# electrosteel2020_10_arrange6_synthboards.net
KiCad netlist of a schematic drawn in EAGLE
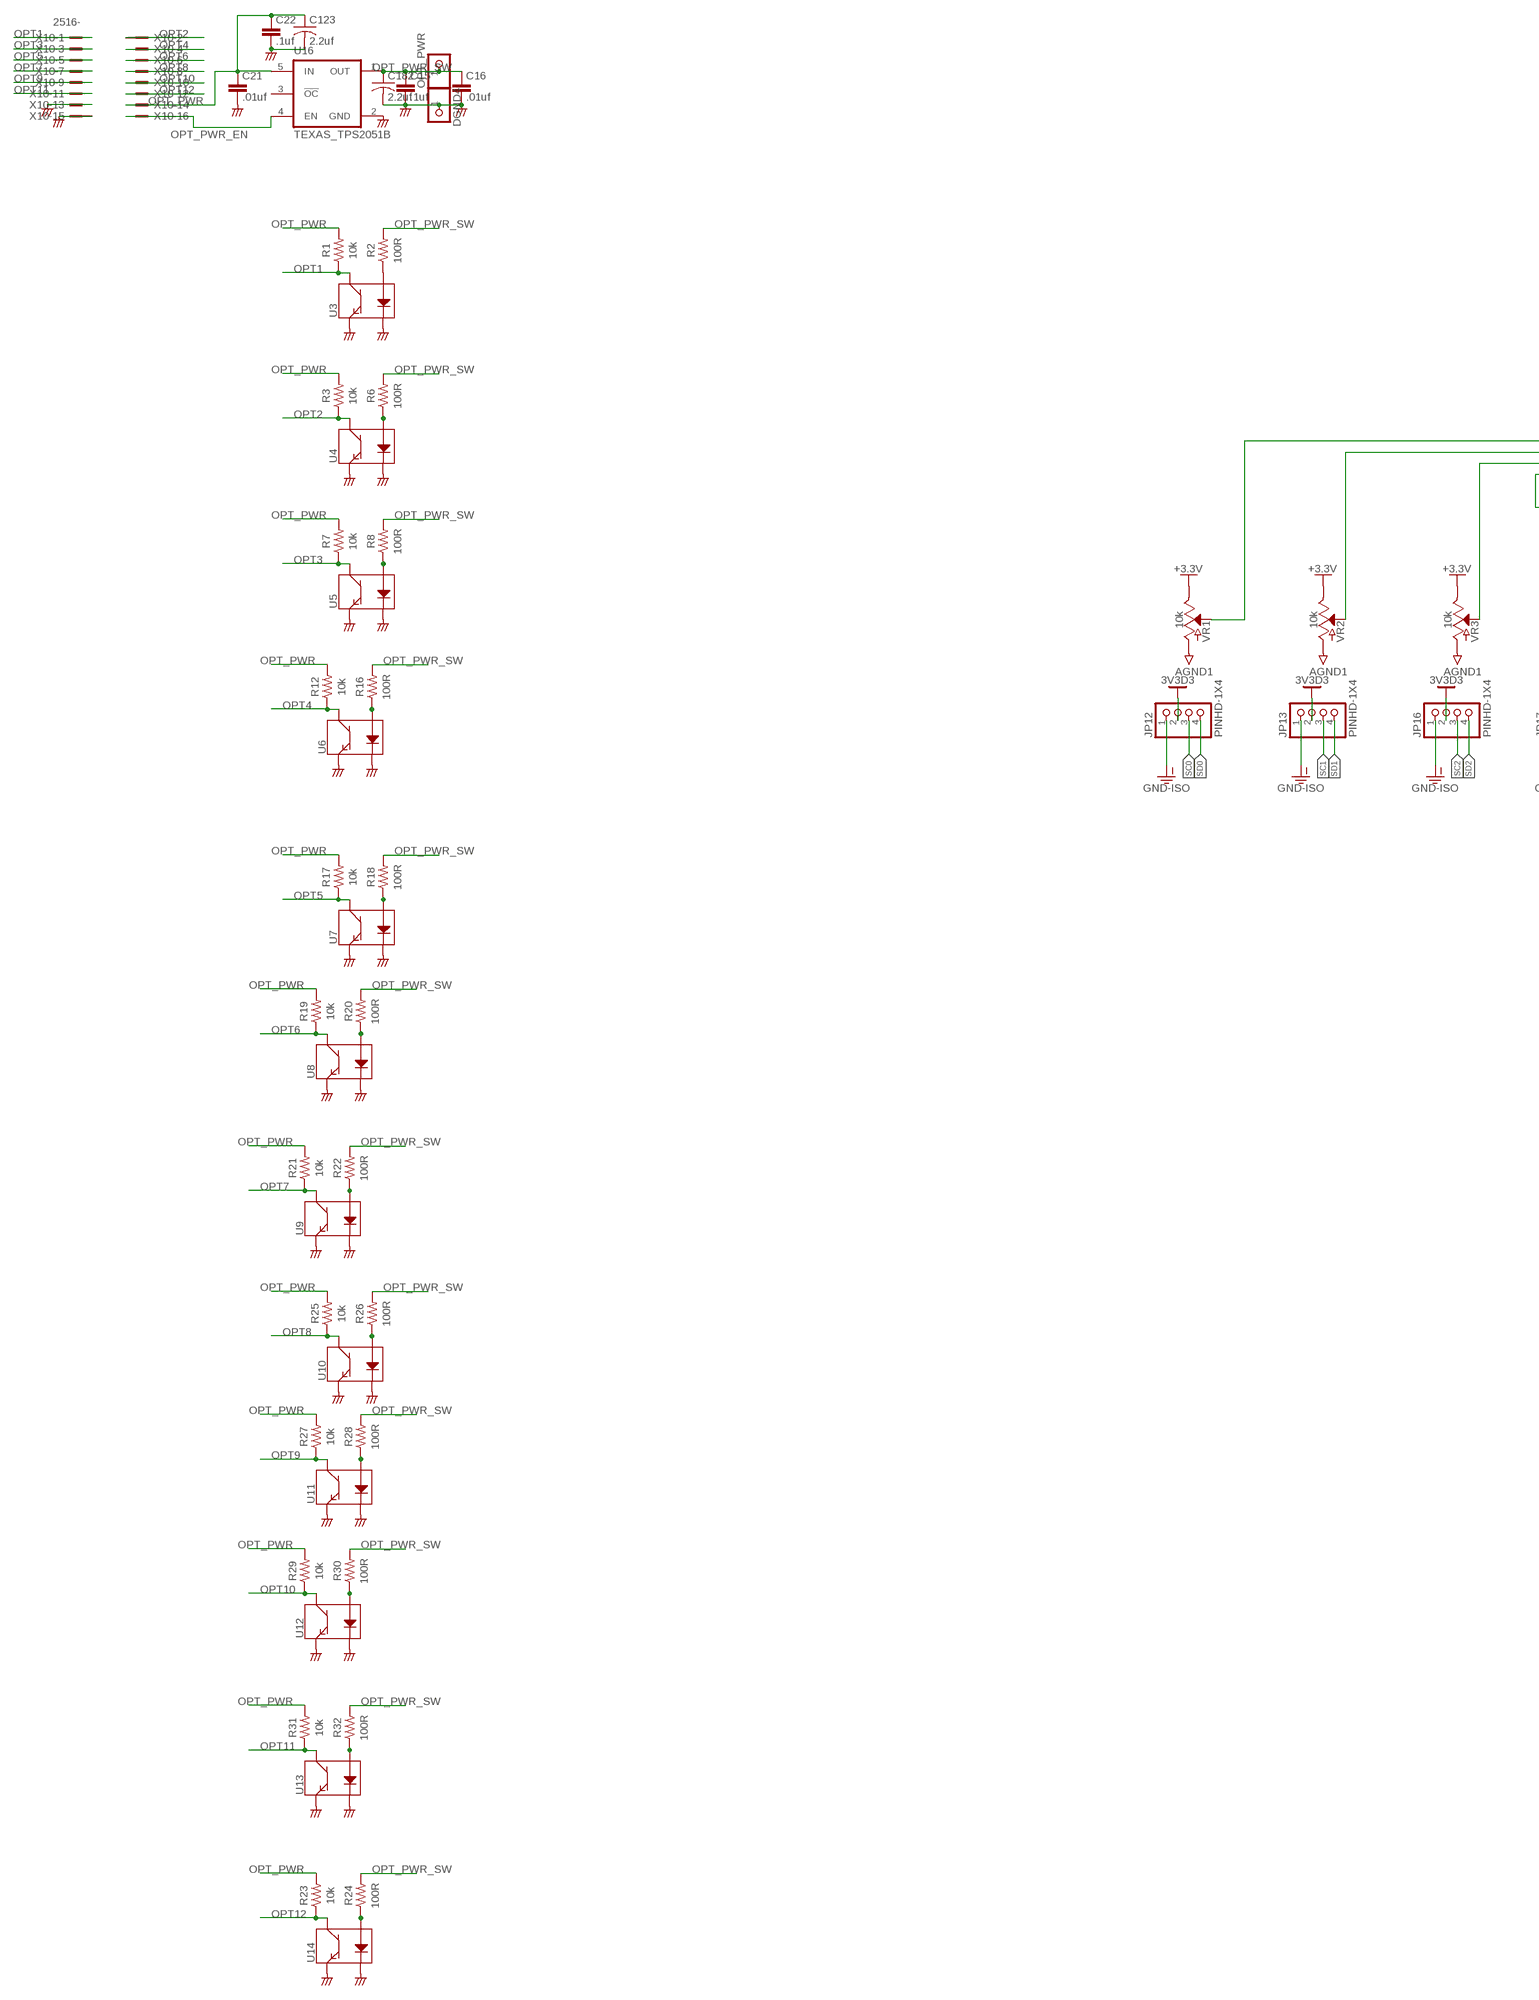
[diagram p0: schematic, sheet 1, part 1 of 3]
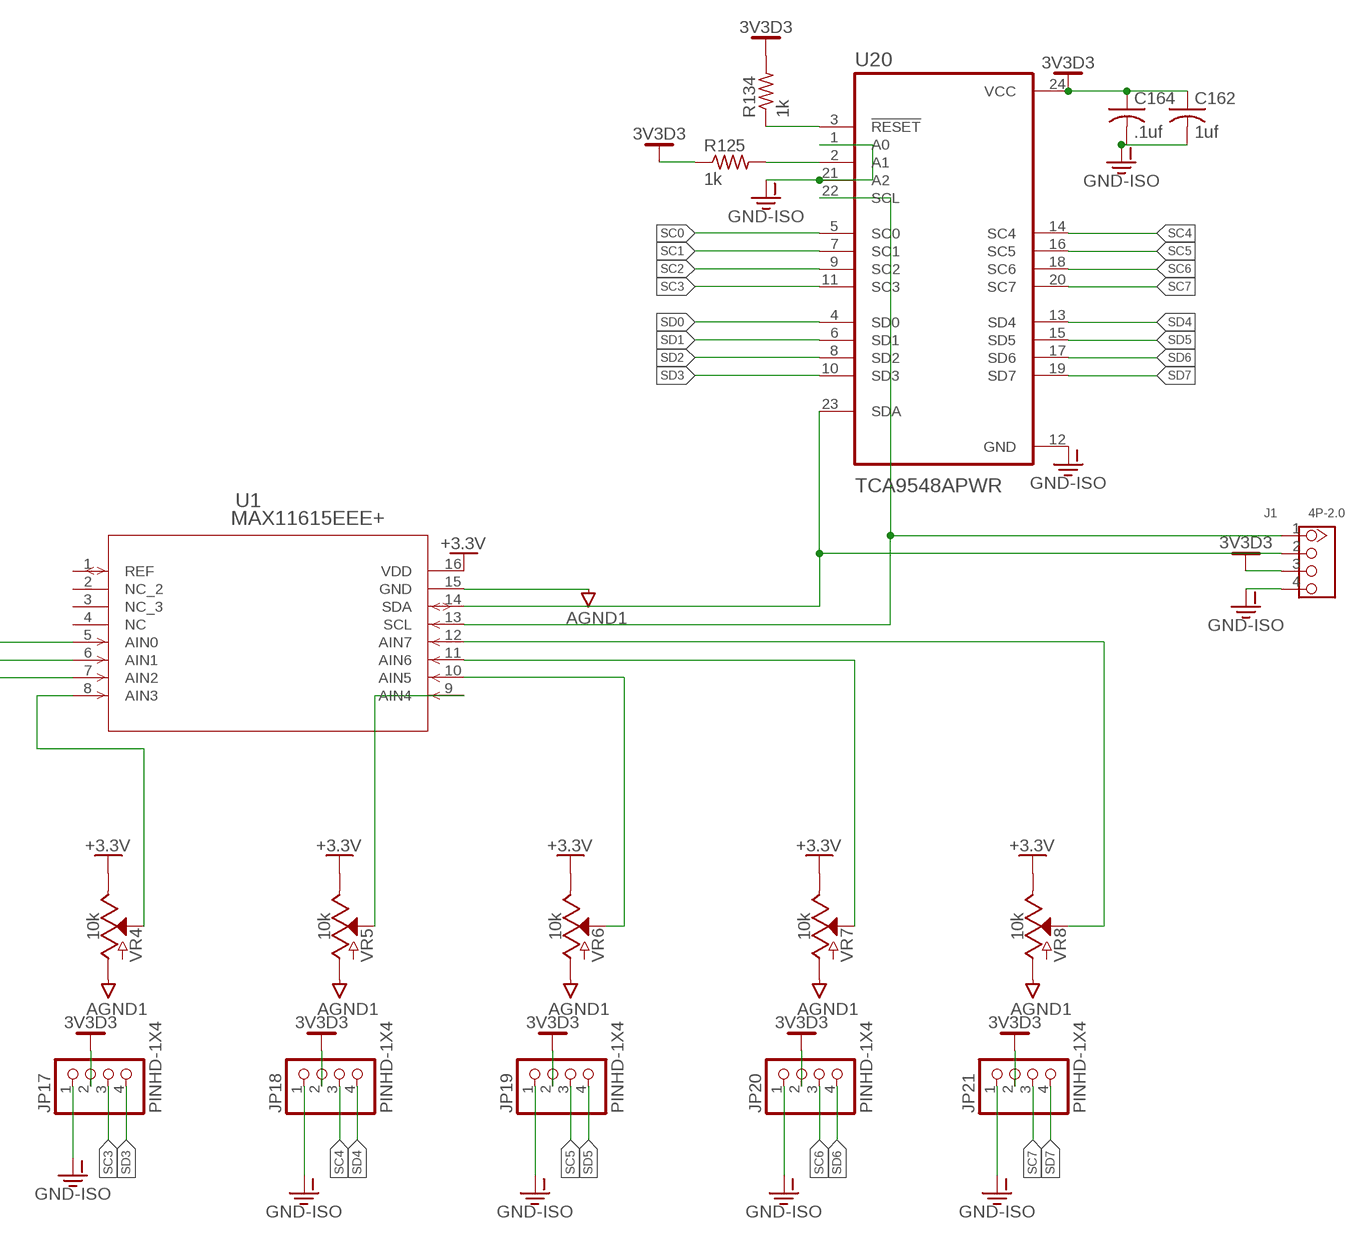
[diagram p1: schematic, sheet 1, part 2 of 3]
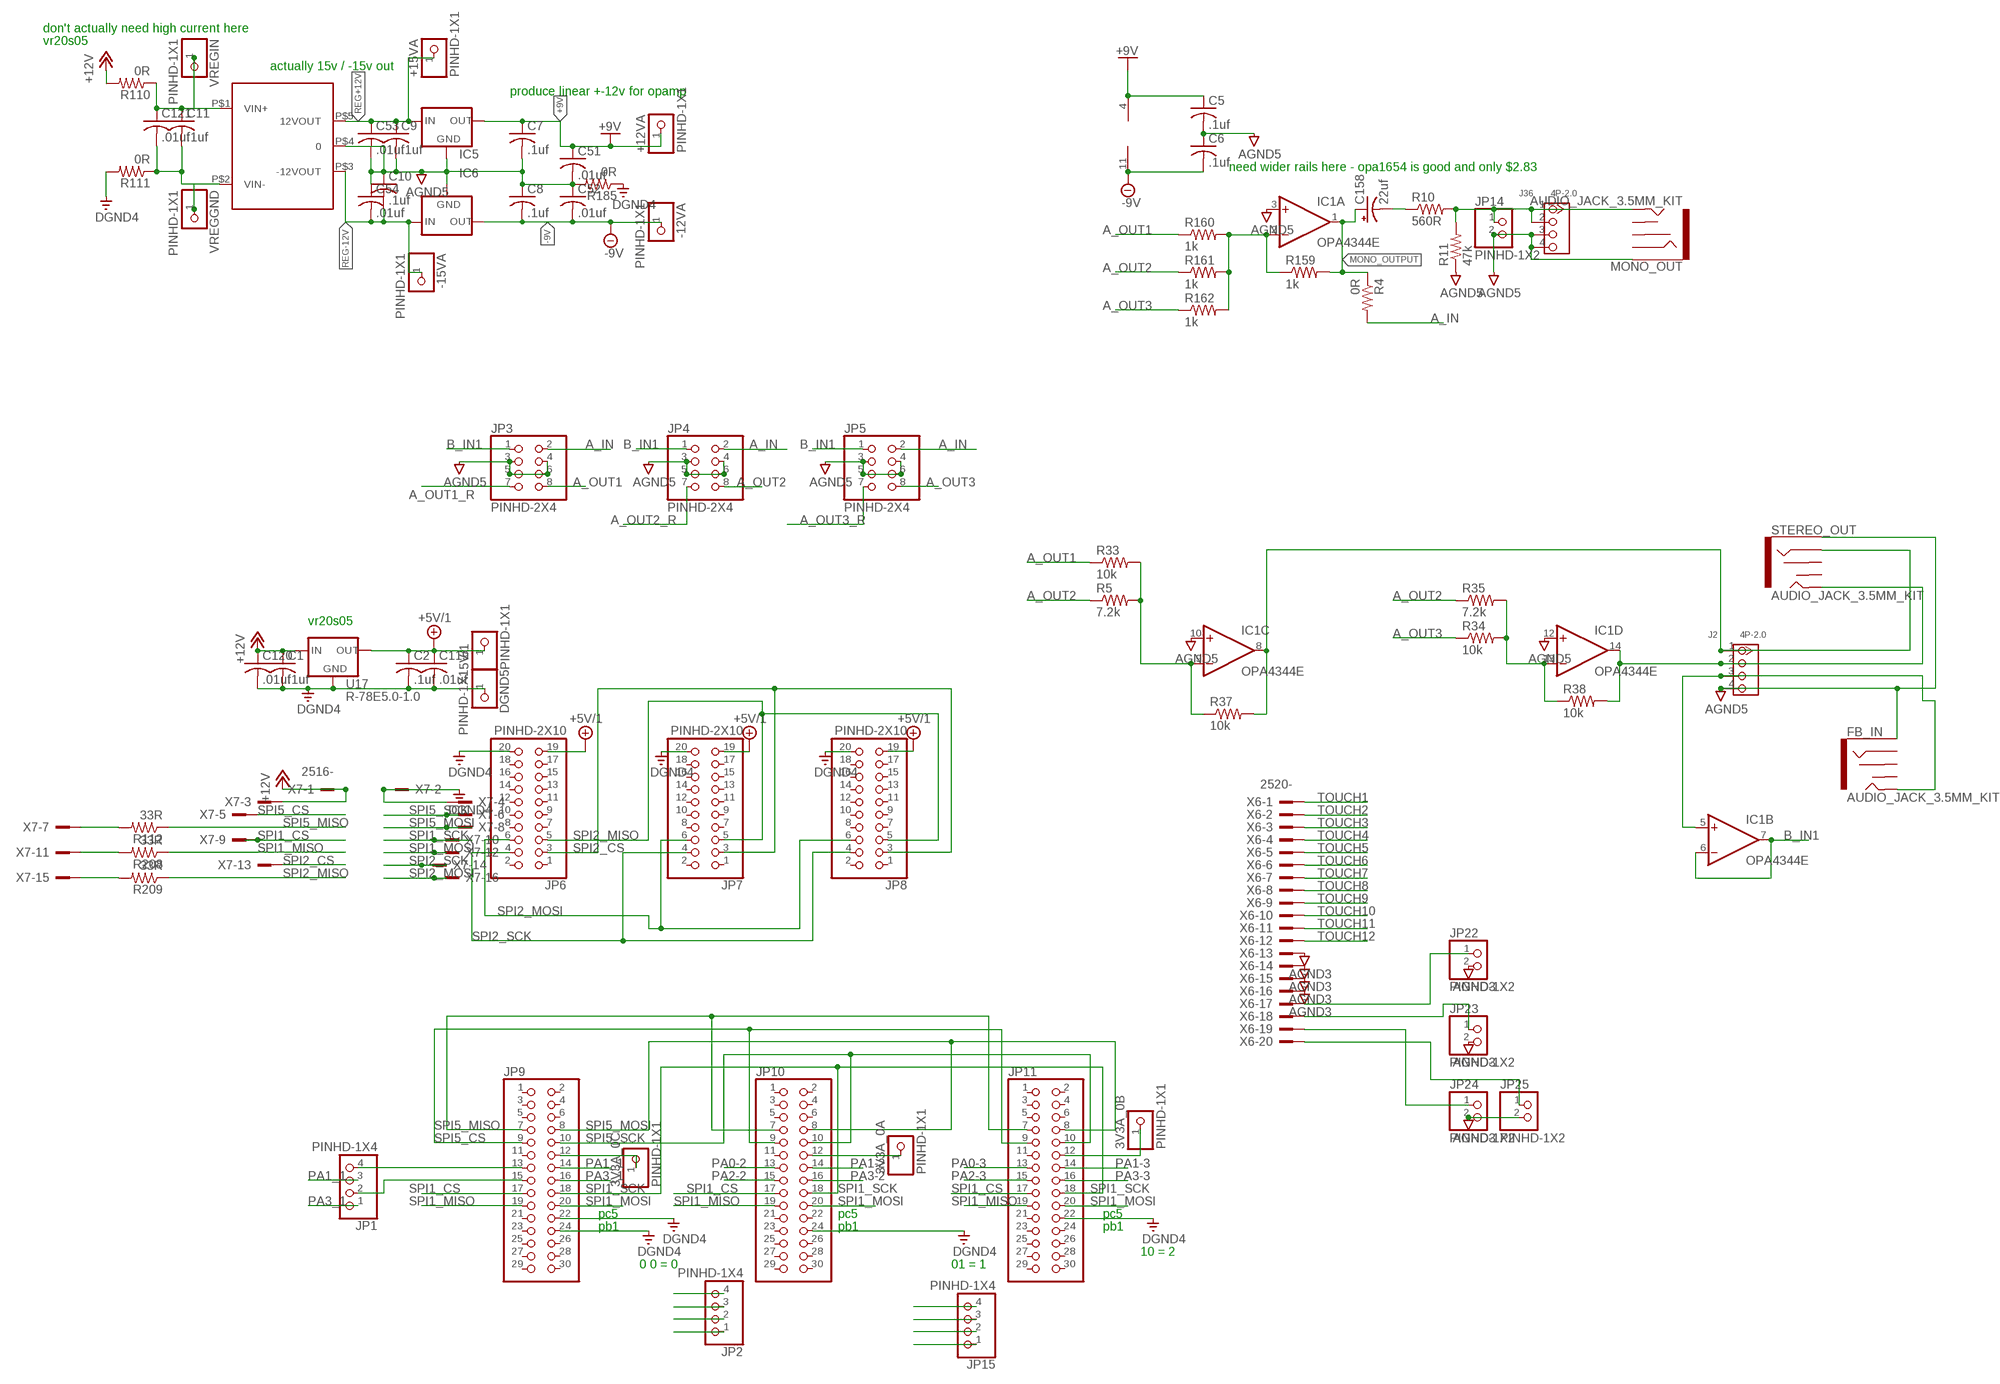
[diagram p2: schematic, sheet 1, part 3 of 3]

(export (version "E")
  (design (tool "Eeschema 10.0.6"))
  (components
    (comp (ref "+12VA")
      (value "PINHD-1X1")
      (footprint "eagle-import:1X01")
      (fields (field (name "PARTNO") "*DNP"))
      (libsource (lib "eagle-import") (part "PINHD-1X1"))
    )
    (comp (ref "+15VA")
      (value "PINHD-1X1")
      (footprint "eagle-import:1X01")
      (fields (field (name "PARTNO") "*DNP"))
      (libsource (lib "eagle-import") (part "PINHD-1X1"))
    )
    (comp (ref "-12VA")
      (value "PINHD-1X1")
      (footprint "eagle-import:1X01")
      (fields (field (name "PARTNO") "*DNP"))
      (libsource (lib "eagle-import") (part "PINHD-1X1"))
    )
    (comp (ref "-15VA")
      (value "PINHD-1X1")
      (footprint "eagle-import:1X01")
      (fields (field (name "PARTNO") "*DNP"))
      (libsource (lib "eagle-import") (part "PINHD-1X1"))
    )
    (comp (ref "3V3A_0A")
      (value "PINHD-1X1")
      (footprint "eagle-import:1X01")
      (fields (field (name "PARTNO") "*DNP"))
      (libsource (lib "eagle-import") (part "PINHD-1X1"))
    )
    (comp (ref "3V3A_0B")
      (value "PINHD-1X1")
      (footprint "eagle-import:1X01")
      (fields (field (name "PARTNO") "*DNP"))
      (libsource (lib "eagle-import") (part "PINHD-1X1"))
    )
    (comp (ref "3V3A_0C")
      (value "PINHD-1X1")
      (footprint "eagle-import:1X01")
      (fields (field (name "PARTNO") "*DNP"))
      (libsource (lib "eagle-import") (part "PINHD-1X1"))
    )
    (comp (ref "5V/1")
      (value "PINHD-1X1")
      (footprint "eagle-import:1X01")
      (fields (field (name "PARTNO") "*DNP"))
      (libsource (lib "eagle-import") (part "PINHD-1X1"))
    )
    (comp (ref "C1")
      (value ".1uf")
      (footprint "eagle-import:C0603")
      (fields (field (name "PARTNO") "TMK063B7103KP-F"))
      (libsource (lib "eagle-import") (part "rcl_334_C-USC0603"))
    )
    (comp (ref "C2")
      (value ".1uf")
      (footprint "eagle-import:C0603")
      (fields (field (name "PARTNO") "TMK063B7103KP-F"))
      (libsource (lib "eagle-import") (part "rcl_334_C-USC0603"))
    )
    (comp (ref "C5")
      (value ".1uf")
      (footprint "eagle-import:C0603")
      (fields (field (name "PARTNO") "TMK063B7103KP-F"))
      (libsource (lib "eagle-import") (part "rcl_334_C-USC0603"))
    )
    (comp (ref "C6")
      (value ".1uf")
      (footprint "eagle-import:C0603")
      (fields (field (name "PARTNO") "TMK063B7103KP-F"))
      (libsource (lib "eagle-import") (part "rcl_334_C-USC0603"))
    )
    (comp (ref "C7")
      (value ".1uf")
      (footprint "eagle-import:C0603")
      (fields (field (name "PARTNO") "TMK063B7103KP-F"))
      (libsource (lib "eagle-import") (part "rcl_334_C-USC0603"))
    )
    (comp (ref "C8")
      (value ".1uf")
      (footprint "eagle-import:C0603")
      (fields (field (name "PARTNO") "TMK063B7103KP-F"))
      (libsource (lib "eagle-import") (part "rcl_334_C-USC0603"))
    )
    (comp (ref "C9")
      (value ".1uf")
      (footprint "eagle-import:C0603")
      (fields (field (name "PARTNO") "TMK063B7103KP-F"))
      (libsource (lib "eagle-import") (part "rcl_334_C-USC0603"))
    )
    (comp (ref "C10")
      (value ".1uf")
      (footprint "eagle-import:C0603")
      (fields (field (name "PARTNO") "TMK063B7103KP-F"))
      (libsource (lib "eagle-import") (part "rcl_334_C-USC0603"))
    )
    (comp (ref "C11")
      (value ".1uf")
      (footprint "eagle-import:C0603")
      (fields (field (name "PARTNO") "TMK063B7103KP-F"))
      (libsource (lib "eagle-import") (part "rcl_334_C-USC0603"))
    )
    (comp (ref "C15")
      (value ".1uf")
      (footprint "eagle-import:0402")
      (fields (field (name "PARTNO") "CC0402KRX7R8BB104"))
      (libsource (lib "eagle-import") (part "CAP_0402"))
    )
    (comp (ref "C16")
      (value ".01uf")
      (footprint "eagle-import:0402")
      (fields (field (name "PARTNO") "CC0402KRX7R8BB103"))
      (libsource (lib "eagle-import") (part "CAP_0402"))
    )
    (comp (ref "C21")
      (value ".01uf")
      (footprint "eagle-import:0402")
      (fields (field (name "PARTNO") "CC0402KRX7R8BB103"))
      (libsource (lib "eagle-import") (part "CAP_0402"))
    )
    (comp (ref "C22")
      (value ".1uf")
      (footprint "eagle-import:0402")
      (fields (field (name "PARTNO") "CC0402KRX7R8BB104"))
      (libsource (lib "eagle-import") (part "CAP_0402"))
    )
    (comp (ref "C51")
      (value ".01uf")
      (footprint "eagle-import:C0603")
      (fields (field (name "PARTNO") "TMK063B7103KP-F"))
      (libsource (lib "eagle-import") (part "rcl_334_C-USC0603"))
    )
    (comp (ref "C52")
      (value ".01uf")
      (footprint "eagle-import:C0603")
      (fields (field (name "PARTNO") "TMK063B7103KP-F"))
      (libsource (lib "eagle-import") (part "rcl_334_C-USC0603"))
    )
    (comp (ref "C53")
      (value ".01uf")
      (footprint "eagle-import:C0603")
      (fields (field (name "PARTNO") "TMK063B7103KP-F"))
      (libsource (lib "eagle-import") (part "rcl_334_C-USC0603"))
    )
    (comp (ref "C54")
      (value ".01uf")
      (footprint "eagle-import:C0603")
      (fields (field (name "PARTNO") "TMK063B7103KP-F"))
      (libsource (lib "eagle-import") (part "rcl_334_C-USC0603"))
    )
    (comp (ref "C119")
      (value ".01uf")
      (footprint "eagle-import:C0603")
      (fields (field (name "PARTNO") "TMK063B7103KP-F"))
      (libsource (lib "eagle-import") (part "rcl_334_C-USC0603"))
    )
    (comp (ref "C120")
      (value ".01uf")
      (footprint "eagle-import:C0603")
      (fields (field (name "PARTNO") "TMK063B7103KP-F"))
      (libsource (lib "eagle-import") (part "rcl_334_C-USC0603"))
    )
    (comp (ref "C121")
      (value ".01uf")
      (footprint "eagle-import:C0603")
      (fields (field (name "PARTNO") "TMK063B7103KP-F"))
      (libsource (lib "eagle-import") (part "rcl_334_C-USC0603"))
    )
    (comp (ref "C123")
      (value "2.2uf")
      (footprint "eagle-import:C1206")
      (fields (field (name "PARTNO") "T491A225K020AT"))
      (libsource (lib "eagle-import") (part "C-USC1206"))
    )
    (comp (ref "C158")
      (value "22uf")
      (footprint "eagle-import:PANASONIC_D")
      (fields (field (name "PARTNO") "EEE-1CA220NP"))
      (libsource (lib "eagle-import") (part "CPOL-USD"))
    )
    (comp (ref "C162")
      (value "1uf")
      (footprint "eagle-import:C1206K")
      (fields (field (name "PARTNO") "C3216X7R1E105K085AA"))
      (libsource (lib "eagle-import") (part "C-USC1206K"))
    )
    (comp (ref "C164")
      (value ".1uf")
      (footprint "eagle-import:C0603K")
      (fields (field (name "PARTNO") "CC0603KRX7R8BB104"))
      (libsource (lib "eagle-import") (part "C-USC0603K"))
    )
    (comp (ref "C182")
      (value "2.2uf")
      (footprint "eagle-import:C1206")
      (fields (field (name "PARTNO") "T491A225K020AT"))
      (libsource (lib "eagle-import") (part "C-USC1206"))
    )
    (comp (ref "DGND4")
      (value "PINHD-1X1")
      (footprint "eagle-import:1X01")
      (fields (field (name "PARTNO") "*DNP"))
      (libsource (lib "eagle-import") (part "adafruit_PINHD-1X1"))
    )
    (comp (ref "DGND5")
      (value "PINHD-1X1")
      (footprint "eagle-import:1X01")
      (fields (field (name "PARTNO") "*DNP"))
      (libsource (lib "eagle-import") (part "PINHD-1X1"))
    )
    (comp (ref "FB_IN")
      (value "AUDIO_JACK_3.5MM_KIT")
      (footprint "eagle-import:AUDIO-JACK-KIT")
      (libsource (lib "eagle-import") (part "AUDIO_JACK_3.5MM_KIT"))
    )
    (comp (ref "IC1")
      (value "OPA4344E")
      (footprint "eagle-import:TSSOP14")
      (fields (field (name "PARTNO") "OPA1654AIPWR"))
      (libsource (lib "eagle-import") (part "OPA4E344"))
    )
    (comp (ref "IC5")
      (value "78LXX")
      (footprint "eagle-import:78LXX")
      (fields (field (name "PARTNO") "LM78L12ACZ/LFT7"))
      (libsource (lib "eagle-import") (part "78LXX"))
    )
    (comp (ref "IC6")
      (value "79LXX")
      (footprint "eagle-import:79LXX")
      (fields (field (name "PARTNO") "L79L12ACZ-TR"))
      (libsource (lib "eagle-import") (part "79LXX"))
    )
    (comp (ref "J1")
      (value "4P-2.0")
      (footprint "eagle-import:HW4-2.0")
      (fields (field (name "PARTNO") "110990030"))
      (libsource (lib "eagle-import") (part "GROVE-CONNECTOR-DIP(4P-2.0)"))
    )
    (comp (ref "J2")
      (value "4P-2.0")
      (footprint "eagle-import:HW4-2.0")
      (fields (field (name "PARTNO") "110990030"))
      (libsource (lib "eagle-import") (part "GROVE-CONNECTOR-DIP(4P-2.0)"))
    )
    (comp (ref "J36")
      (value "4P-2.0")
      (footprint "eagle-import:HW4-2.0")
      (fields (field (name "PARTNO") "110990030"))
      (libsource (lib "eagle-import") (part "GROVE-CONNECTOR-DIP(4P-2.0)"))
    )
    (comp (ref "JP1")
      (value "PINHD-1X4")
      (footprint "eagle-import:1X04")
      (libsource (lib "eagle-import") (part "PINHD-1X4"))
    )
    (comp (ref "JP2")
      (value "PINHD-1X4")
      (footprint "eagle-import:1X04")
      (libsource (lib "eagle-import") (part "PINHD-1X4"))
    )
    (comp (ref "JP3")
      (value "PINHD-2X4")
      (footprint "eagle-import:2X04")
      (fields (field (name "PARTNO") "77313-101-08LF"))
      (libsource (lib "eagle-import") (part "PINHD-2X4"))
    )
    (comp (ref "JP4")
      (value "PINHD-2X4")
      (footprint "eagle-import:2X04")
      (fields (field (name "PARTNO") "77313-101-08LF"))
      (libsource (lib "eagle-import") (part "PINHD-2X4"))
    )
    (comp (ref "JP5")
      (value "PINHD-2X4")
      (footprint "eagle-import:2X04")
      (fields (field (name "PARTNO") "77313-101-08LF"))
      (libsource (lib "eagle-import") (part "PINHD-2X4"))
    )
    (comp (ref "JP6")
      (value "PINHD-2X10")
      (footprint "eagle-import:2X10")
      (fields (field (name "PARTNO") "77313-101-20LF"))
      (libsource (lib "eagle-import") (part "PINHD-2X10"))
    )
    (comp (ref "JP7")
      (value "PINHD-2X10")
      (footprint "eagle-import:2X10")
      (fields (field (name "PARTNO") "77313-101-20LF"))
      (libsource (lib "eagle-import") (part "PINHD-2X10"))
    )
    (comp (ref "JP8")
      (value "PINHD-2X10")
      (footprint "eagle-import:2X10")
      (fields (field (name "PARTNO") "77313-101-20LF"))
      (libsource (lib "eagle-import") (part "PINHD-2X10"))
    )
    (comp (ref "JP9")
      (value "PINHD-2X15")
      (footprint "eagle-import:2X15")
      (fields (field (name "PARTNO") "77313-101-30LF"))
      (libsource (lib "eagle-import") (part "PINHD-2X15"))
    )
    (comp (ref "JP10")
      (value "PINHD-2X15")
      (footprint "eagle-import:2X15")
      (fields (field (name "PARTNO") "77313-101-30LF"))
      (libsource (lib "eagle-import") (part "PINHD-2X15"))
    )
    (comp (ref "JP11")
      (value "PINHD-2X15")
      (footprint "eagle-import:2X15")
      (fields (field (name "PARTNO") "77313-101-30LF"))
      (libsource (lib "eagle-import") (part "PINHD-2X15"))
    )
    (comp (ref "JP12")
      (value "PINHD-1X4")
      (footprint "eagle-import:1X04")
      (libsource (lib "eagle-import") (part "PINHD-1X4"))
    )
    (comp (ref "JP13")
      (value "PINHD-1X4")
      (footprint "eagle-import:1X04")
      (libsource (lib "eagle-import") (part "PINHD-1X4"))
    )
    (comp (ref "JP14")
      (value "PINHD-1X2")
      (footprint "eagle-import:1X02")
      (fields (field (name "PARTNO") "*DNP"))
      (libsource (lib "eagle-import") (part "PINHD-1X2"))
    )
    (comp (ref "JP15")
      (value "PINHD-1X4")
      (footprint "eagle-import:1X04")
      (libsource (lib "eagle-import") (part "PINHD-1X4"))
    )
    (comp (ref "JP16")
      (value "PINHD-1X4")
      (footprint "eagle-import:1X04")
      (libsource (lib "eagle-import") (part "PINHD-1X4"))
    )
    (comp (ref "JP17")
      (value "PINHD-1X4")
      (footprint "eagle-import:1X04")
      (libsource (lib "eagle-import") (part "PINHD-1X4"))
    )
    (comp (ref "JP18")
      (value "PINHD-1X4")
      (footprint "eagle-import:1X04")
      (libsource (lib "eagle-import") (part "PINHD-1X4"))
    )
    (comp (ref "JP19")
      (value "PINHD-1X4")
      (footprint "eagle-import:1X04")
      (libsource (lib "eagle-import") (part "PINHD-1X4"))
    )
    (comp (ref "JP20")
      (value "PINHD-1X4")
      (footprint "eagle-import:1X04")
      (libsource (lib "eagle-import") (part "PINHD-1X4"))
    )
    (comp (ref "JP21")
      (value "PINHD-1X4")
      (footprint "eagle-import:1X04")
      (libsource (lib "eagle-import") (part "PINHD-1X4"))
    )
    (comp (ref "JP22")
      (value "PINHD-1X2")
      (footprint "eagle-import:1X02")
      (fields (field (name "PARTNO") "*DNP"))
      (libsource (lib "eagle-import") (part "PINHD-1X2"))
    )
    (comp (ref "JP23")
      (value "PINHD-1X2")
      (footprint "eagle-import:1X02")
      (fields (field (name "PARTNO") "*DNP"))
      (libsource (lib "eagle-import") (part "PINHD-1X2"))
    )
    (comp (ref "JP24")
      (value "PINHD-1X2")
      (footprint "eagle-import:1X02")
      (fields (field (name "PARTNO") "*DNP"))
      (libsource (lib "eagle-import") (part "PINHD-1X2"))
    )
    (comp (ref "JP25")
      (value "PINHD-1X2")
      (footprint "eagle-import:1X02")
      (fields (field (name "PARTNO") "*DNP"))
      (libsource (lib "eagle-import") (part "PINHD-1X2"))
    )
    (comp (ref "MONO_OUT")
      (value "AUDIO_JACK_3.5MM_KIT")
      (footprint "eagle-import:AUDIO-JACK-KIT")
      (libsource (lib "eagle-import") (part "AUDIO_JACK_3.5MM_KIT"))
    )
    (comp (ref "OPT_PWR")
      (value "PINHD-1X1")
      (footprint "eagle-import:1X01")
      (fields (field (name "PARTNO") "*DNP"))
      (libsource (lib "eagle-import") (part "adafruit_PINHD-1X1"))
    )
    (comp (ref "R1")
      (value "10k")
      (footprint "eagle-import:RESC1608X60")
      (fields (field (name "PARTNO") "ESR03EZPF1002"))
      (libsource (lib "eagle-import") (part "R-USCHIP-0603(1608-METRIC)_"))
    )
    (comp (ref "R2")
      (value "100R")
      (footprint "eagle-import:RESC1608X60")
      (fields (field (name "PARTNO") "ESR03EZPJ101"))
      (libsource (lib "eagle-import") (part "R-USCHIP-0603(1608-METRIC)_"))
    )
    (comp (ref "R3")
      (value "10k")
      (footprint "eagle-import:RESC1608X60")
      (fields (field (name "PARTNO") "ESR03EZPF1002"))
      (libsource (lib "eagle-import") (part "R-USCHIP-0603(1608-METRIC)_"))
    )
    (comp (ref "R4")
      (value "0R")
      (footprint "eagle-import:R0603")
      (fields (field (name "PARTNO") "RCS06030000Z0EA"))
      (libsource (lib "eagle-import") (part "R-US_R0603"))
    )
    (comp (ref "R5")
      (value "7.2k")
      (footprint "eagle-import:R0603")
      (fields (field (name "PARTNO") "ESR03EZPF1001"))
      (libsource (lib "eagle-import") (part "R-US_R0603"))
    )
    (comp (ref "R6")
      (value "100R")
      (footprint "eagle-import:RESC1608X60")
      (fields (field (name "PARTNO") "ESR03EZPJ101"))
      (libsource (lib "eagle-import") (part "R-USCHIP-0603(1608-METRIC)_"))
    )
    (comp (ref "R7")
      (value "10k")
      (footprint "eagle-import:RESC1608X60")
      (fields (field (name "PARTNO") "ESR03EZPF1002"))
      (libsource (lib "eagle-import") (part "R-USCHIP-0603(1608-METRIC)_"))
    )
    (comp (ref "R8")
      (value "100R")
      (footprint "eagle-import:RESC1608X60")
      (fields (field (name "PARTNO") "ESR03EZPJ101"))
      (libsource (lib "eagle-import") (part "R-USCHIP-0603(1608-METRIC)_"))
    )
    (comp (ref "R10")
      (value "560R")
      (footprint "eagle-import:R0603")
      (fields (field (name "PARTNO") "ESR03EZPF5600"))
      (libsource (lib "eagle-import") (part "R-US_R0603"))
    )
    (comp (ref "R11")
      (value "47k")
      (footprint "eagle-import:R0603")
      (fields (field (name "PARTNO") "ESR03EZPJ473"))
      (libsource (lib "eagle-import") (part "R-US_R0603"))
    )
    (comp (ref "R12")
      (value "10k")
      (footprint "eagle-import:RESC1608X60")
      (fields (field (name "PARTNO") "ESR03EZPF1002"))
      (libsource (lib "eagle-import") (part "R-USCHIP-0603(1608-METRIC)_"))
    )
    (comp (ref "R16")
      (value "100R")
      (footprint "eagle-import:RESC1608X60")
      (fields (field (name "PARTNO") "ESR03EZPJ101"))
      (libsource (lib "eagle-import") (part "R-USCHIP-0603(1608-METRIC)_"))
    )
    (comp (ref "R17")
      (value "10k")
      (footprint "eagle-import:RESC1608X60")
      (fields (field (name "PARTNO") "ESR03EZPF1002"))
      (libsource (lib "eagle-import") (part "R-USCHIP-0603(1608-METRIC)_"))
    )
    (comp (ref "R18")
      (value "100R")
      (footprint "eagle-import:RESC1608X60")
      (fields (field (name "PARTNO") "ESR03EZPJ101"))
      (libsource (lib "eagle-import") (part "R-USCHIP-0603(1608-METRIC)_"))
    )
    (comp (ref "R19")
      (value "10k")
      (footprint "eagle-import:RESC1608X60")
      (fields (field (name "PARTNO") "ESR03EZPF1002"))
      (libsource (lib "eagle-import") (part "R-USCHIP-0603(1608-METRIC)_"))
    )
    (comp (ref "R20")
      (value "100R")
      (footprint "eagle-import:RESC1608X60")
      (fields (field (name "PARTNO") "ESR03EZPJ101"))
      (libsource (lib "eagle-import") (part "R-USCHIP-0603(1608-METRIC)_"))
    )
    (comp (ref "R21")
      (value "10k")
      (footprint "eagle-import:RESC1608X60")
      (fields (field (name "PARTNO") "ESR03EZPF1002"))
      (libsource (lib "eagle-import") (part "R-USCHIP-0603(1608-METRIC)_"))
    )
    (comp (ref "R22")
      (value "100R")
      (footprint "eagle-import:RESC1608X60")
      (fields (field (name "PARTNO") "ESR03EZPJ101"))
      (libsource (lib "eagle-import") (part "R-USCHIP-0603(1608-METRIC)_"))
    )
    (comp (ref "R23")
      (value "10k")
      (footprint "eagle-import:RESC1608X60")
      (fields (field (name "PARTNO") "ESR03EZPF1002"))
      (libsource (lib "eagle-import") (part "R-USCHIP-0603(1608-METRIC)_"))
    )
    (comp (ref "R24")
      (value "100R")
      (footprint "eagle-import:RESC1608X60")
      (fields (field (name "PARTNO") "ESR03EZPJ101"))
      (libsource (lib "eagle-import") (part "R-USCHIP-0603(1608-METRIC)_"))
    )
    (comp (ref "R25")
      (value "10k")
      (footprint "eagle-import:RESC1608X60")
      (fields (field (name "PARTNO") "ESR03EZPF1002"))
      (libsource (lib "eagle-import") (part "R-USCHIP-0603(1608-METRIC)_"))
    )
    (comp (ref "R26")
      (value "100R")
      (footprint "eagle-import:RESC1608X60")
      (fields (field (name "PARTNO") "ESR03EZPJ101"))
      (libsource (lib "eagle-import") (part "R-USCHIP-0603(1608-METRIC)_"))
    )
    (comp (ref "R27")
      (value "10k")
      (footprint "eagle-import:RESC1608X60")
      (fields (field (name "PARTNO") "ESR03EZPF1002"))
      (libsource (lib "eagle-import") (part "R-USCHIP-0603(1608-METRIC)_"))
    )
    (comp (ref "R28")
      (value "100R")
      (footprint "eagle-import:RESC1608X60")
      (fields (field (name "PARTNO") "ESR03EZPJ101"))
      (libsource (lib "eagle-import") (part "R-USCHIP-0603(1608-METRIC)_"))
    )
    (comp (ref "R29")
      (value "10k")
      (footprint "eagle-import:RESC1608X60")
      (fields (field (name "PARTNO") "ESR03EZPF1002"))
      (libsource (lib "eagle-import") (part "R-USCHIP-0603(1608-METRIC)_"))
    )
    (comp (ref "R30")
      (value "100R")
      (footprint "eagle-import:RESC1608X60")
      (fields (field (name "PARTNO") "ESR03EZPJ101"))
      (libsource (lib "eagle-import") (part "R-USCHIP-0603(1608-METRIC)_"))
    )
    (comp (ref "R31")
      (value "10k")
      (footprint "eagle-import:RESC1608X60")
      (fields (field (name "PARTNO") "ESR03EZPF1002"))
      (libsource (lib "eagle-import") (part "R-USCHIP-0603(1608-METRIC)_"))
    )
    (comp (ref "R32")
      (value "100R")
      (footprint "eagle-import:RESC1608X60")
      (fields (field (name "PARTNO") "ESR03EZPJ101"))
      (libsource (lib "eagle-import") (part "R-USCHIP-0603(1608-METRIC)_"))
    )
    (comp (ref "R33")
      (value "10k")
      (footprint "eagle-import:R0603")
      (fields (field (name "PARTNO") "ESR03EZPF1001"))
      (libsource (lib "eagle-import") (part "R-US_R0603"))
    )
    (comp (ref "R34")
      (value "10k")
      (footprint "eagle-import:R0603")
      (fields (field (name "PARTNO") "ESR03EZPF1001"))
      (libsource (lib "eagle-import") (part "R-US_R0603"))
    )
    (comp (ref "R35")
      (value "7.2k")
      (footprint "eagle-import:R0603")
      (fields (field (name "PARTNO") "ESR03EZPF1001"))
      (libsource (lib "eagle-import") (part "R-US_R0603"))
    )
    (comp (ref "R37")
      (value "10k")
      (footprint "eagle-import:R0603")
      (fields (field (name "PARTNO") "ESR03EZPF1001"))
      (libsource (lib "eagle-import") (part "R-US_R0603"))
    )
    (comp (ref "R38")
      (value "10k")
      (footprint "eagle-import:R0603")
      (fields (field (name "PARTNO") "ESR03EZPF1001"))
      (libsource (lib "eagle-import") (part "R-US_R0603"))
    )
    (comp (ref "R110")
      (value "0R")
      (footprint "eagle-import:R0603")
      (fields (field (name "PARTNO") "RCS06030000Z0EA"))
      (libsource (lib "eagle-import") (part "R-US_R0603"))
    )
    (comp (ref "R111")
      (value "0R")
      (footprint "eagle-import:R0603")
      (fields (field (name "PARTNO") "RCS06030000Z0EA"))
      (libsource (lib "eagle-import") (part "R-US_R0603"))
    )
    (comp (ref "R112")
      (value "33R")
      (footprint "eagle-import:R0603")
      (fields (field (name "PARTNO") "RC0201FR-0733RL"))
      (libsource (lib "eagle-import") (part "rcl_334_R-US_R0603"))
    )
    (comp (ref "R125")
      (value "1k")
      (footprint "eagle-import:R0603")
      (fields (field (name "PARTNO") "ESR03EZPF1001"))
      (libsource (lib "eagle-import") (part "R-US_R0603"))
    )
    (comp (ref "R134")
      (value "1k")
      (footprint "eagle-import:R0603")
      (fields (field (name "PARTNO") "ESR03EZPF1001"))
      (libsource (lib "eagle-import") (part "R-US_R0603"))
    )
    (comp (ref "R159")
      (value "1k")
      (footprint "eagle-import:R0603")
      (fields (field (name "PARTNO") "ESR03EZPF1001"))
      (libsource (lib "eagle-import") (part "R-US_R0603"))
    )
    (comp (ref "R160")
      (value "1k")
      (footprint "eagle-import:R0603")
      (fields (field (name "PARTNO") "ESR03EZPF1001"))
      (libsource (lib "eagle-import") (part "R-US_R0603"))
    )
    (comp (ref "R161")
      (value "1k")
      (footprint "eagle-import:R0603")
      (fields (field (name "PARTNO") "ESR03EZPF1001"))
      (libsource (lib "eagle-import") (part "R-US_R0603"))
    )
    (comp (ref "R162")
      (value "1k")
      (footprint "eagle-import:R0603")
      (fields (field (name "PARTNO") "ESR03EZPF1001"))
      (libsource (lib "eagle-import") (part "R-US_R0603"))
    )
    (comp (ref "R185")
      (value "0R")
      (footprint "eagle-import:R0603")
      (fields (field (name "PARTNO") "RCS06030000Z0EA"))
      (libsource (lib "eagle-import") (part "R-US_R0603"))
    )
    (comp (ref "R208")
      (value "33R")
      (footprint "eagle-import:R0603")
      (fields (field (name "PARTNO") "RC0201FR-0733RL"))
      (libsource (lib "eagle-import") (part "rcl_334_R-US_R0603"))
    )
    (comp (ref "R209")
      (value "33R")
      (footprint "eagle-import:R0603")
      (fields (field (name "PARTNO") "RC0201FR-0733RL"))
      (libsource (lib "eagle-import") (part "rcl_334_R-US_R0603"))
    )
    (comp (ref "STEREO_OUT")
      (value "AUDIO_JACK_3.5MM_KIT")
      (footprint "eagle-import:AUDIO-JACK-KIT")
      (libsource (lib "eagle-import") (part "AUDIO_JACK_3.5MM_KIT"))
    )
    (comp (ref "U$3")
      (value "CMR0512S3C")
      (footprint "eagle-import:CMR0512S3C")
      (fields (field (name "PARTNO") "DPU01M-15"))
      (libsource (lib "eagle-import") (part "CMR0512S3C"))
    )
    (comp (ref "U1")
      (value "MAX11615EEE+")
      (footprint "eagle-import:21-0055H_16_MXM")
      (fields (field (name "MANUFACTURER_PART_NUMBER") "max11615eee+"))
      (libsource (lib "eagle-import") (part "MAX11615EEE+"))
    )
    (comp (ref "U3")
      (value "QRE1113")
      (footprint "eagle-import:QRE1113")
      (fields (field (name "PARTNO") "QRE1113GR"))
      (libsource (lib "eagle-import") (part "QRE1113"))
    )
    (comp (ref "U4")
      (value "QRE1113")
      (footprint "eagle-import:QRE1113")
      (fields (field (name "PARTNO") "QRE1113GR"))
      (libsource (lib "eagle-import") (part "QRE1113"))
    )
    (comp (ref "U5")
      (value "QRE1113")
      (footprint "eagle-import:QRE1113")
      (fields (field (name "PARTNO") "QRE1113GR"))
      (libsource (lib "eagle-import") (part "QRE1113"))
    )
    (comp (ref "U6")
      (value "QRE1113")
      (footprint "eagle-import:QRE1113")
      (fields (field (name "PARTNO") "QRE1113GR"))
      (libsource (lib "eagle-import") (part "QRE1113"))
    )
    (comp (ref "U7")
      (value "QRE1113")
      (footprint "eagle-import:QRE1113")
      (fields (field (name "PARTNO") "QRE1113GR"))
      (libsource (lib "eagle-import") (part "QRE1113"))
    )
    (comp (ref "U8")
      (value "QRE1113")
      (footprint "eagle-import:QRE1113")
      (fields (field (name "PARTNO") "QRE1113GR"))
      (libsource (lib "eagle-import") (part "QRE1113"))
    )
    (comp (ref "U9")
      (value "QRE1113")
      (footprint "eagle-import:QRE1113")
      (fields (field (name "PARTNO") "QRE1113GR"))
      (libsource (lib "eagle-import") (part "QRE1113"))
    )
    (comp (ref "U10")
      (value "QRE1113")
      (footprint "eagle-import:QRE1113")
      (fields (field (name "PARTNO") "QRE1113GR"))
      (libsource (lib "eagle-import") (part "QRE1113"))
    )
    (comp (ref "U11")
      (value "QRE1113")
      (footprint "eagle-import:QRE1113")
      (fields (field (name "PARTNO") "QRE1113GR"))
      (libsource (lib "eagle-import") (part "QRE1113"))
    )
    (comp (ref "U12")
      (value "QRE1113")
      (footprint "eagle-import:QRE1113")
      (fields (field (name "PARTNO") "QRE1113GR"))
      (libsource (lib "eagle-import") (part "QRE1113"))
    )
    (comp (ref "U13")
      (value "QRE1113")
      (footprint "eagle-import:QRE1113")
      (fields (field (name "PARTNO") "QRE1113GR"))
      (libsource (lib "eagle-import") (part "QRE1113"))
    )
    (comp (ref "U14")
      (value "QRE1113")
      (footprint "eagle-import:QRE1113")
      (fields (field (name "PARTNO") "QRE1113GR"))
      (libsource (lib "eagle-import") (part "QRE1113"))
    )
    (comp (ref "U16")
      (value "TEXAS_TPS2051B")
      (footprint "eagle-import:TEXAS_SOT23-5")
      (fields (field (name "PARTNO") "TPS2051BDBVRG4"))
      (libsource (lib "eagle-import") (part "TEXAS_TPS2051B"))
    )
    (comp (ref "U17")
      (value "R-78E5.0-1.0")
      (footprint "eagle-import:DC-DC_CONVERTER_78XX")
      (libsource (lib "eagle-import") (part "R-78E5.0-1.0"))
    )
    (comp (ref "U20")
      (value "TCA9548APWR")
      (footprint "eagle-import:SOP65P640X120-24N")
      (fields (field (name "MF") "Texas Instruments"))
      (libsource (lib "eagle-import") (part "TCA9548APWR"))
    )
    (comp (ref "VR1")
      (value "10k")
      (footprint "eagle-import:POT-PTH-ALPS")
      (libsource (lib "eagle-import") (part "POTENTIOMETER-PTH-9MM-1/20W-20%"))
    )
    (comp (ref "VR2")
      (value "10k")
      (footprint "eagle-import:POT-PTH-ALPS")
      (libsource (lib "eagle-import") (part "POTENTIOMETER-PTH-9MM-1/20W-20%"))
    )
    (comp (ref "VR3")
      (value "10k")
      (footprint "eagle-import:POT-PTH-ALPS")
      (libsource (lib "eagle-import") (part "POTENTIOMETER-PTH-9MM-1/20W-20%"))
    )
    (comp (ref "VR4")
      (value "10k")
      (footprint "eagle-import:POT-PTH-ALPS")
      (libsource (lib "eagle-import") (part "POTENTIOMETER-PTH-9MM-1/20W-20%"))
    )
    (comp (ref "VR5")
      (value "10k")
      (footprint "eagle-import:POT-PTH-ALPS")
      (libsource (lib "eagle-import") (part "POTENTIOMETER-PTH-9MM-1/20W-20%"))
    )
    (comp (ref "VR6")
      (value "10k")
      (footprint "eagle-import:POT-PTH-ALPS")
      (libsource (lib "eagle-import") (part "POTENTIOMETER-PTH-9MM-1/20W-20%"))
    )
    (comp (ref "VR7")
      (value "10k")
      (footprint "eagle-import:POT-PTH-ALPS")
      (libsource (lib "eagle-import") (part "POTENTIOMETER-PTH-9MM-1/20W-20%"))
    )
    (comp (ref "VR8")
      (value "10k")
      (footprint "eagle-import:POT-PTH-ALPS")
      (libsource (lib "eagle-import") (part "POTENTIOMETER-PTH-9MM-1/20W-20%"))
    )
    (comp (ref "VREGGND")
      (value "PINHD-1X1")
      (footprint "eagle-import:1X01")
      (fields (field (name "PARTNO") "*DNP"))
      (libsource (lib "eagle-import") (part "PINHD-1X1"))
    )
    (comp (ref "VREGIN")
      (value "PINHD-1X1")
      (footprint "eagle-import:1X01")
      (fields (field (name "PARTNO") "*DNP"))
      (libsource (lib "eagle-import") (part "PINHD-1X1"))
    )
    (comp (ref "X6")
      (value "2520-")
      (footprint "eagle-import:PAK100_2500-20")
      (fields (field (name "PARTNO") "N2520-6003-UG"))
      (libsource (lib "eagle-import") (part "2520-"))
    )
    (comp (ref "X7")
      (value "2516-")
      (footprint "eagle-import:PAK100_2500-16")
      (fields (field (name "PARTNO") "D2516-6002-AR"))
      (libsource (lib "eagle-import") (part "2516-"))
    )
    (comp (ref "X10")
      (value "2516-")
      (footprint "eagle-import:PAK100_2500-16")
      (fields (field (name "PARTNO") "D2516-6002-AR"))
      (libsource (lib "eagle-import") (part "2516-"))
    )
  )
  (nets
    (net (code "1") (name "+3.3V") (class "Default")
      (node (ref "U1") (pin "16") (pinfunction "VDD_16") (pintype "power_in"))
      (node (ref "VR1") (pin "P$1") (pinfunction "E_P$1") (pintype "passive"))
      (node (ref "VR2") (pin "P$1") (pinfunction "E_P$1") (pintype "passive"))
      (node (ref "VR3") (pin "P$1") (pinfunction "E_P$1") (pintype "passive"))
      (node (ref "VR4") (pin "P$1") (pinfunction "E_P$1") (pintype "passive"))
      (node (ref "VR5") (pin "P$1") (pinfunction "E_P$1") (pintype "passive"))
      (node (ref "VR6") (pin "P$1") (pinfunction "E_P$1") (pintype "passive"))
      (node (ref "VR7") (pin "P$1") (pinfunction "E_P$1") (pintype "passive"))
      (node (ref "VR8") (pin "P$1") (pinfunction "E_P$1") (pintype "passive"))
    )
    (net (code "2") (name "+5V{slash}1") (class "Default")
      (node (ref "5V/1") (pin "1") (pinfunction "1_1") (pintype "passive"))
      (node (ref "C119") (pin "1") (pinfunction "1_1") (pintype "passive"))
      (node (ref "C2") (pin "1") (pinfunction "1_1") (pintype "passive"))
      (node (ref "JP6") (pin "19") (pinfunction "19_19") (pintype "passive"))
      (node (ref "JP7") (pin "19") (pinfunction "19_19") (pintype "passive"))
      (node (ref "JP8") (pin "19") (pinfunction "19_19") (pintype "passive"))
      (node (ref "U17") (pin "VOUT") (pinfunction "OUT_VOUT") (pintype "passive"))
    )
    (net (code "3") (name "+9V") (class "Default")
      (node (ref "+12VA") (pin "1") (pinfunction "1_1") (pintype "passive"))
      (node (ref "C5") (pin "1") (pinfunction "1_1") (pintype "passive"))
      (node (ref "C51") (pin "1") (pinfunction "1_1") (pintype "passive"))
      (node (ref "C7") (pin "1") (pinfunction "1_1") (pintype "passive"))
      (node (ref "IC1") (pin "4") (pinfunction "V+_4") (pintype "power_in"))
      (node (ref "IC5") (pin "OUT") (pinfunction "OUT_OUT") (pintype "passive"))
    )
    (net (code "4") (name "+12V") (class "Default")
      (node (ref "C1") (pin "1") (pinfunction "1_1") (pintype "passive"))
      (node (ref "C120") (pin "1") (pinfunction "1_1") (pintype "passive"))
      (node (ref "R110") (pin "2") (pinfunction "2_2") (pintype "passive"))
      (node (ref "U17") (pin "VIN") (pinfunction "IN_VIN") (pintype "input"))
      (node (ref "X7") (pin "1") (pinfunction "KL_1") (pintype "passive"))
      (node (ref "X7") (pin "3") (pinfunction "KL_3") (pintype "passive"))
    )
    (net (code "5") (name "-9V") (class "Default")
      (node (ref "-12VA") (pin "1") (pinfunction "1_1") (pintype "passive"))
      (node (ref "C52") (pin "2") (pinfunction "2_2") (pintype "passive"))
      (node (ref "C6") (pin "2") (pinfunction "2_2") (pintype "passive"))
      (node (ref "C8") (pin "2") (pinfunction "2_2") (pintype "passive"))
      (node (ref "IC1") (pin "11") (pinfunction "V-_11") (pintype "power_in"))
      (node (ref "IC6") (pin "OUT") (pinfunction "OUT_OUT") (pintype "passive"))
    )
    (net (code "6") (name "/A_IN") (class "Default")
      (node (ref "JP3") (pin "2") (pinfunction "2_2") (pintype "passive"))
      (node (ref "JP4") (pin "2") (pinfunction "2_2") (pintype "passive"))
      (node (ref "JP5") (pin "2") (pinfunction "2_2") (pintype "passive"))
      (node (ref "R4") (pin "2") (pinfunction "2_2") (pintype "passive"))
    )
    (net (code "7") (name "/A_OUT1") (class "Default")
      (node (ref "JP3") (pin "8") (pinfunction "8_8") (pintype "passive"))
      (node (ref "R160") (pin "1") (pinfunction "1_1") (pintype "passive"))
      (node (ref "R33") (pin "1") (pinfunction "1_1") (pintype "passive"))
    )
    (net (code "8") (name "/A_OUT1_R") (class "Default")
      (node (ref "JP3") (pin "7") (pinfunction "7_7") (pintype "passive"))
    )
    (net (code "9") (name "/A_OUT2") (class "Default")
      (node (ref "JP4") (pin "8") (pinfunction "8_8") (pintype "passive"))
      (node (ref "R161") (pin "1") (pinfunction "1_1") (pintype "passive"))
      (node (ref "R35") (pin "1") (pinfunction "1_1") (pintype "passive"))
      (node (ref "R5") (pin "1") (pinfunction "1_1") (pintype "passive"))
    )
    (net (code "10") (name "/A_OUT2_R") (class "Default")
      (node (ref "JP4") (pin "7") (pinfunction "7_7") (pintype "passive"))
    )
    (net (code "11") (name "/A_OUT3") (class "Default")
      (node (ref "JP5") (pin "8") (pinfunction "8_8") (pintype "passive"))
      (node (ref "R162") (pin "1") (pinfunction "1_1") (pintype "passive"))
      (node (ref "R34") (pin "1") (pinfunction "1_1") (pintype "passive"))
    )
    (net (code "12") (name "/A_OUT3_R") (class "Default")
      (node (ref "JP5") (pin "7") (pinfunction "7_7") (pintype "passive"))
    )
    (net (code "13") (name "/B_IN1") (class "Default")
      (node (ref "IC1") (pin "6") (pinfunction "-IN_6") (pintype "input"))
      (node (ref "IC1") (pin "7") (pinfunction "OUT_7") (pintype "output"))
      (node (ref "JP3") (pin "1") (pinfunction "1_1") (pintype "passive"))
      (node (ref "JP4") (pin "1") (pinfunction "1_1") (pintype "passive"))
      (node (ref "JP5") (pin "1") (pinfunction "1_1") (pintype "passive"))
    )
    (net (code "14") (name "/OPT1") (class "Default")
      (node (ref "R1") (pin "1") (pinfunction "1_1") (pintype "passive"))
      (node (ref "U3") (pin "3") (pinfunction "C_3") (pintype "bidirectional"))
      (node (ref "X10") (pin "1") (pinfunction "KL_1") (pintype "passive"))
    )
    (net (code "15") (name "/OPT2") (class "Default")
      (node (ref "R3") (pin "1") (pinfunction "1_1") (pintype "passive"))
      (node (ref "U4") (pin "3") (pinfunction "C_3") (pintype "bidirectional"))
      (node (ref "X10") (pin "2") (pinfunction "KL_2") (pintype "passive"))
    )
    (net (code "16") (name "/OPT3") (class "Default")
      (node (ref "R7") (pin "1") (pinfunction "1_1") (pintype "passive"))
      (node (ref "U5") (pin "3") (pinfunction "C_3") (pintype "bidirectional"))
      (node (ref "X10") (pin "3") (pinfunction "KL_3") (pintype "passive"))
    )
    (net (code "17") (name "/OPT4") (class "Default")
      (node (ref "R12") (pin "1") (pinfunction "1_1") (pintype "passive"))
      (node (ref "U6") (pin "3") (pinfunction "C_3") (pintype "bidirectional"))
      (node (ref "X10") (pin "4") (pinfunction "KL_4") (pintype "passive"))
    )
    (net (code "18") (name "/OPT5") (class "Default")
      (node (ref "R17") (pin "1") (pinfunction "1_1") (pintype "passive"))
      (node (ref "U7") (pin "3") (pinfunction "C_3") (pintype "bidirectional"))
      (node (ref "X10") (pin "5") (pinfunction "KL_5") (pintype "passive"))
    )
    (net (code "19") (name "/OPT6") (class "Default")
      (node (ref "R19") (pin "1") (pinfunction "1_1") (pintype "passive"))
      (node (ref "U8") (pin "3") (pinfunction "C_3") (pintype "bidirectional"))
      (node (ref "X10") (pin "6") (pinfunction "KL_6") (pintype "passive"))
    )
    (net (code "20") (name "/OPT7") (class "Default")
      (node (ref "R21") (pin "1") (pinfunction "1_1") (pintype "passive"))
      (node (ref "U9") (pin "3") (pinfunction "C_3") (pintype "bidirectional"))
      (node (ref "X10") (pin "7") (pinfunction "KL_7") (pintype "passive"))
    )
    (net (code "21") (name "/OPT8") (class "Default")
      (node (ref "R25") (pin "1") (pinfunction "1_1") (pintype "passive"))
      (node (ref "U10") (pin "3") (pinfunction "C_3") (pintype "bidirectional"))
      (node (ref "X10") (pin "8") (pinfunction "KL_8") (pintype "passive"))
    )
    (net (code "22") (name "/OPT9") (class "Default")
      (node (ref "R27") (pin "1") (pinfunction "1_1") (pintype "passive"))
      (node (ref "U11") (pin "3") (pinfunction "C_3") (pintype "bidirectional"))
      (node (ref "X10") (pin "9") (pinfunction "KL_9") (pintype "passive"))
    )
    (net (code "23") (name "/OPT10") (class "Default")
      (node (ref "R29") (pin "1") (pinfunction "1_1") (pintype "passive"))
      (node (ref "U12") (pin "3") (pinfunction "C_3") (pintype "bidirectional"))
      (node (ref "X10") (pin "10") (pinfunction "KL_10") (pintype "passive"))
    )
    (net (code "24") (name "/OPT11") (class "Default")
      (node (ref "R31") (pin "1") (pinfunction "1_1") (pintype "passive"))
      (node (ref "U13") (pin "3") (pinfunction "C_3") (pintype "bidirectional"))
      (node (ref "X10") (pin "11") (pinfunction "KL_11") (pintype "passive"))
    )
    (net (code "25") (name "/OPT12") (class "Default")
      (node (ref "R23") (pin "1") (pinfunction "1_1") (pintype "passive"))
      (node (ref "U14") (pin "3") (pinfunction "C_3") (pintype "bidirectional"))
      (node (ref "X10") (pin "12") (pinfunction "KL_12") (pintype "passive"))
    )
    (net (code "26") (name "/OPT_PWR") (class "Default")
      (node (ref "C123") (pin "1") (pinfunction "1_1") (pintype "passive"))
      (node (ref "C21") (pin "1") (pinfunction "1_1") (pintype "passive"))
      (node (ref "C22") (pin "1") (pinfunction "1_1") (pintype "passive"))
      (node (ref "R1") (pin "2") (pinfunction "2_2") (pintype "passive"))
      (node (ref "R12") (pin "2") (pinfunction "2_2") (pintype "passive"))
      (node (ref "R17") (pin "2") (pinfunction "2_2") (pintype "passive"))
      (node (ref "R19") (pin "2") (pinfunction "2_2") (pintype "passive"))
      (node (ref "R21") (pin "2") (pinfunction "2_2") (pintype "passive"))
      (node (ref "R23") (pin "2") (pinfunction "2_2") (pintype "passive"))
      (node (ref "R25") (pin "2") (pinfunction "2_2") (pintype "passive"))
      (node (ref "R27") (pin "2") (pinfunction "2_2") (pintype "passive"))
      (node (ref "R29") (pin "2") (pinfunction "2_2") (pintype "passive"))
      (node (ref "R3") (pin "2") (pinfunction "2_2") (pintype "passive"))
      (node (ref "R31") (pin "2") (pinfunction "2_2") (pintype "passive"))
      (node (ref "R7") (pin "2") (pinfunction "2_2") (pintype "passive"))
      (node (ref "U16") (pin "5") (pinfunction "IN_5") (pintype "input"))
      (node (ref "X10") (pin "14") (pinfunction "KL_14") (pintype "passive"))
    )
    (net (code "27") (name "/OPT_PWR_EN") (class "Default")
      (node (ref "U16") (pin "4") (pinfunction "EN_4") (pintype "input"))
      (node (ref "X10") (pin "16") (pinfunction "KL_16") (pintype "passive"))
    )
    (net (code "28") (name "/OPT_PWR_SW") (class "Default")
      (node (ref "C15") (pin "1") (pinfunction "1_1") (pintype "passive"))
      (node (ref "C16") (pin "1") (pinfunction "1_1") (pintype "passive"))
      (node (ref "C182") (pin "1") (pinfunction "1_1") (pintype "passive"))
      (node (ref "OPT_PWR") (pin "1") (pinfunction "1_1") (pintype "passive"))
      (node (ref "R16") (pin "2") (pinfunction "2_2") (pintype "passive"))
      (node (ref "R18") (pin "2") (pinfunction "2_2") (pintype "passive"))
      (node (ref "R2") (pin "2") (pinfunction "2_2") (pintype "passive"))
      (node (ref "R20") (pin "2") (pinfunction "2_2") (pintype "passive"))
      (node (ref "R22") (pin "2") (pinfunction "2_2") (pintype "passive"))
      (node (ref "R24") (pin "2") (pinfunction "2_2") (pintype "passive"))
      (node (ref "R26") (pin "2") (pinfunction "2_2") (pintype "passive"))
      (node (ref "R28") (pin "2") (pinfunction "2_2") (pintype "passive"))
      (node (ref "R30") (pin "2") (pinfunction "2_2") (pintype "passive"))
      (node (ref "R32") (pin "2") (pinfunction "2_2") (pintype "passive"))
      (node (ref "R6") (pin "2") (pinfunction "2_2") (pintype "passive"))
      (node (ref "R8") (pin "2") (pinfunction "2_2") (pintype "passive"))
      (node (ref "U16") (pin "1") (pinfunction "OUT_1") (pintype "passive"))
    )
    (net (code "29") (name "/PA0-2") (class "Default")
      (node (ref "JP10") (pin "13") (pinfunction "13_13") (pintype "passive"))
      (node (ref "JP2") (pin "4") (pinfunction "4_4") (pintype "passive"))
    )
    (net (code "30") (name "/PA0-3") (class "Default")
      (node (ref "JP11") (pin "13") (pinfunction "13_13") (pintype "passive"))
      (node (ref "JP15") (pin "4") (pinfunction "4_4") (pintype "passive"))
    )
    (net (code "31") (name "/PA1-2") (class "Default")
      (node (ref "JP10") (pin "14") (pinfunction "14_14") (pintype "passive"))
      (node (ref "JP2") (pin "3") (pinfunction "3_3") (pintype "passive"))
    )
    (net (code "32") (name "/PA1-3") (class "Default")
      (node (ref "JP11") (pin "14") (pinfunction "14_14") (pintype "passive"))
      (node (ref "JP15") (pin "3") (pinfunction "3_3") (pintype "passive"))
    )
    (net (code "33") (name "/PA1_1") (class "Default")
      (node (ref "JP1") (pin "3") (pinfunction "3_3") (pintype "passive"))
      (node (ref "JP9") (pin "14") (pinfunction "14_14") (pintype "passive"))
    )
    (net (code "34") (name "/PA2-2") (class "Default")
      (node (ref "JP10") (pin "15") (pinfunction "15_15") (pintype "passive"))
      (node (ref "JP2") (pin "2") (pinfunction "2_2") (pintype "passive"))
    )
    (net (code "35") (name "/PA2-3") (class "Default")
      (node (ref "JP11") (pin "15") (pinfunction "15_15") (pintype "passive"))
      (node (ref "JP15") (pin "2") (pinfunction "2_2") (pintype "passive"))
    )
    (net (code "36") (name "/PA3-2") (class "Default")
      (node (ref "JP10") (pin "16") (pinfunction "16_16") (pintype "passive"))
      (node (ref "JP2") (pin "1") (pinfunction "1_1") (pintype "passive"))
    )
    (net (code "37") (name "/PA3-3") (class "Default")
      (node (ref "JP11") (pin "16") (pinfunction "16_16") (pintype "passive"))
      (node (ref "JP15") (pin "1") (pinfunction "1_1") (pintype "passive"))
    )
    (net (code "38") (name "/PA3_1") (class "Default")
      (node (ref "JP1") (pin "1") (pinfunction "1_1") (pintype "passive"))
      (node (ref "JP9") (pin "16") (pinfunction "16_16") (pintype "passive"))
    )
    (net (code "39") (name "/SPI1_CS") (class "Default")
      (node (ref "JP10") (pin "17") (pinfunction "17_17") (pintype "passive"))
      (node (ref "JP11") (pin "17") (pinfunction "17_17") (pintype "passive"))
      (node (ref "JP9") (pin "17") (pinfunction "17_17") (pintype "passive"))
      (node (ref "X7") (pin "9") (pinfunction "KL_9") (pintype "passive"))
    )
    (net (code "40") (name "/SPI1_MISO") (class "Default")
      (node (ref "JP10") (pin "19") (pinfunction "19_19") (pintype "passive"))
      (node (ref "JP11") (pin "19") (pinfunction "19_19") (pintype "passive"))
      (node (ref "JP9") (pin "19") (pinfunction "19_19") (pintype "passive"))
      (node (ref "R208") (pin "1") (pinfunction "1_1") (pintype "passive"))
    )
    (net (code "41") (name "/SPI1_MOSI") (class "Default")
      (node (ref "JP10") (pin "20") (pinfunction "20_20") (pintype "passive"))
      (node (ref "JP11") (pin "20") (pinfunction "20_20") (pintype "passive"))
      (node (ref "JP9") (pin "20") (pinfunction "20_20") (pintype "passive"))
      (node (ref "X7") (pin "12") (pinfunction "KL_12") (pintype "passive"))
    )
    (net (code "42") (name "/SPI1_SCK") (class "Default")
      (node (ref "JP10") (pin "18") (pinfunction "18_18") (pintype "passive"))
      (node (ref "JP11") (pin "18") (pinfunction "18_18") (pintype "passive"))
      (node (ref "JP9") (pin "18") (pinfunction "18_18") (pintype "passive"))
      (node (ref "X7") (pin "10") (pinfunction "KL_10") (pintype "passive"))
    )
    (net (code "43") (name "/SPI2_CS") (class "Default")
      (node (ref "JP6") (pin "3") (pinfunction "3_3") (pintype "passive"))
      (node (ref "JP7") (pin "3") (pinfunction "3_3") (pintype "passive"))
      (node (ref "JP8") (pin "3") (pinfunction "3_3") (pintype "passive"))
      (node (ref "X7") (pin "13") (pinfunction "KL_13") (pintype "passive"))
    )
    (net (code "44") (name "/SPI2_MISO") (class "Default")
      (node (ref "JP6") (pin "5") (pinfunction "5_5") (pintype "passive"))
      (node (ref "JP7") (pin "5") (pinfunction "5_5") (pintype "passive"))
      (node (ref "JP8") (pin "5") (pinfunction "5_5") (pintype "passive"))
      (node (ref "R209") (pin "1") (pinfunction "1_1") (pintype "passive"))
    )
    (net (code "45") (name "/SPI2_MOSI") (class "Default")
      (node (ref "JP6") (pin "6") (pinfunction "6_6") (pintype "passive"))
      (node (ref "JP7") (pin "6") (pinfunction "6_6") (pintype "passive"))
      (node (ref "JP8") (pin "6") (pinfunction "6_6") (pintype "passive"))
      (node (ref "X7") (pin "16") (pinfunction "KL_16") (pintype "passive"))
    )
    (net (code "46") (name "/SPI2_SCK") (class "Default")
      (node (ref "JP6") (pin "4") (pinfunction "4_4") (pintype "passive"))
      (node (ref "JP7") (pin "4") (pinfunction "4_4") (pintype "passive"))
      (node (ref "JP8") (pin "4") (pinfunction "4_4") (pintype "passive"))
      (node (ref "X7") (pin "14") (pinfunction "KL_14") (pintype "passive"))
    )
    (net (code "47") (name "/SPI5_CS") (class "Default")
      (node (ref "JP10") (pin "9") (pinfunction "9_9") (pintype "passive"))
      (node (ref "JP11") (pin "9") (pinfunction "9_9") (pintype "passive"))
      (node (ref "JP9") (pin "9") (pinfunction "9_9") (pintype "passive"))
      (node (ref "X7") (pin "5") (pinfunction "KL_5") (pintype "passive"))
    )
    (net (code "48") (name "/SPI5_MISO") (class "Default")
      (node (ref "JP10") (pin "7") (pinfunction "7_7") (pintype "passive"))
      (node (ref "JP11") (pin "7") (pinfunction "7_7") (pintype "passive"))
      (node (ref "JP9") (pin "7") (pinfunction "7_7") (pintype "passive"))
      (node (ref "R112") (pin "1") (pinfunction "1_1") (pintype "passive"))
    )
    (net (code "49") (name "/SPI5_MOSI") (class "Default")
      (node (ref "JP10") (pin "8") (pinfunction "8_8") (pintype "passive"))
      (node (ref "JP11") (pin "8") (pinfunction "8_8") (pintype "passive"))
      (node (ref "JP9") (pin "8") (pinfunction "8_8") (pintype "passive"))
      (node (ref "X7") (pin "8") (pinfunction "KL_8") (pintype "passive"))
    )
    (net (code "50") (name "/SPI5_SCK") (class "Default")
      (node (ref "JP10") (pin "10") (pinfunction "10_10") (pintype "passive"))
      (node (ref "JP11") (pin "10") (pinfunction "10_10") (pintype "passive"))
      (node (ref "JP9") (pin "10") (pinfunction "10_10") (pintype "passive"))
      (node (ref "X7") (pin "6") (pinfunction "KL_6") (pintype "passive"))
    )
    (net (code "51") (name "/TOUCH1") (class "Default")
      (node (ref "X6") (pin "1") (pinfunction "KL_1") (pintype "passive"))
    )
    (net (code "52") (name "/TOUCH2") (class "Default")
      (node (ref "X6") (pin "2") (pinfunction "KL_2") (pintype "passive"))
    )
    (net (code "53") (name "/TOUCH3") (class "Default")
      (node (ref "X6") (pin "3") (pinfunction "KL_3") (pintype "passive"))
    )
    (net (code "54") (name "/TOUCH4") (class "Default")
      (node (ref "X6") (pin "4") (pinfunction "KL_4") (pintype "passive"))
    )
    (net (code "55") (name "/TOUCH5") (class "Default")
      (node (ref "X6") (pin "5") (pinfunction "KL_5") (pintype "passive"))
    )
    (net (code "56") (name "/TOUCH6") (class "Default")
      (node (ref "X6") (pin "6") (pinfunction "KL_6") (pintype "passive"))
    )
    (net (code "57") (name "/TOUCH7") (class "Default")
      (node (ref "X6") (pin "7") (pinfunction "KL_7") (pintype "passive"))
    )
    (net (code "58") (name "/TOUCH8") (class "Default")
      (node (ref "X6") (pin "8") (pinfunction "KL_8") (pintype "passive"))
    )
    (net (code "59") (name "/TOUCH9") (class "Default")
      (node (ref "X6") (pin "9") (pinfunction "KL_9") (pintype "passive"))
    )
    (net (code "60") (name "/TOUCH10") (class "Default")
      (node (ref "X6") (pin "10") (pinfunction "KL_10") (pintype "passive"))
    )
    (net (code "61") (name "/TOUCH11") (class "Default")
      (node (ref "X6") (pin "11") (pinfunction "KL_11") (pintype "passive"))
    )
    (net (code "62") (name "/TOUCH12") (class "Default")
      (node (ref "X6") (pin "12") (pinfunction "KL_12") (pintype "passive"))
    )
    (net (code "63") (name "3V3D3") (class "Default")
      (node (ref "C162") (pin "1") (pinfunction "1_1") (pintype "passive"))
      (node (ref "C164") (pin "1") (pinfunction "1_1") (pintype "passive"))
      (node (ref "J1") (pin "3") (pinfunction "3_3") (pintype "bidirectional"))
      (node (ref "JP12") (pin "2") (pinfunction "2_2") (pintype "passive"))
      (node (ref "JP13") (pin "2") (pinfunction "2_2") (pintype "passive"))
      (node (ref "JP16") (pin "2") (pinfunction "2_2") (pintype "passive"))
      (node (ref "JP17") (pin "2") (pinfunction "2_2") (pintype "passive"))
      (node (ref "JP18") (pin "2") (pinfunction "2_2") (pintype "passive"))
      (node (ref "JP19") (pin "2") (pinfunction "2_2") (pintype "passive"))
      (node (ref "JP20") (pin "2") (pinfunction "2_2") (pintype "passive"))
      (node (ref "JP21") (pin "2") (pinfunction "2_2") (pintype "passive"))
      (node (ref "R125") (pin "1") (pinfunction "1_1") (pintype "passive"))
      (node (ref "R134") (pin "2") (pinfunction "2_2") (pintype "passive"))
      (node (ref "U20") (pin "24") (pinfunction "VCC_24") (pintype "power_in"))
    )
    (net (code "64") (name "AGND1") (class "Default")
      (node (ref "U1") (pin "15") (pinfunction "GND_15") (pintype "power_in"))
      (node (ref "VR1") (pin "P$3") (pinfunction "A_P$3") (pintype "passive"))
      (node (ref "VR2") (pin "P$3") (pinfunction "A_P$3") (pintype "passive"))
      (node (ref "VR3") (pin "P$3") (pinfunction "A_P$3") (pintype "passive"))
      (node (ref "VR4") (pin "P$3") (pinfunction "A_P$3") (pintype "passive"))
      (node (ref "VR5") (pin "P$3") (pinfunction "A_P$3") (pintype "passive"))
      (node (ref "VR6") (pin "P$3") (pinfunction "A_P$3") (pintype "passive"))
      (node (ref "VR7") (pin "P$3") (pinfunction "A_P$3") (pintype "passive"))
      (node (ref "VR8") (pin "P$3") (pinfunction "A_P$3") (pintype "passive"))
    )
    (net (code "65") (name "AGND3") (class "Default")
      (node (ref "JP22") (pin "2") (pinfunction "2_2") (pintype "passive"))
      (node (ref "JP23") (pin "2") (pinfunction "2_2") (pintype "passive"))
      (node (ref "JP24") (pin "2") (pinfunction "2_2") (pintype "passive"))
      (node (ref "JP25") (pin "2") (pinfunction "2_2") (pintype "passive"))
      (node (ref "X6") (pin "13") (pinfunction "KL_13") (pintype "passive"))
      (node (ref "X6") (pin "14") (pinfunction "KL_14") (pintype "passive"))
      (node (ref "X6") (pin "15") (pinfunction "KL_15") (pintype "passive"))
      (node (ref "X6") (pin "16") (pinfunction "KL_16") (pintype "passive"))
    )
    (net (code "66") (name "AGND5") (class "Default")
      (node (ref "C10") (pin "1") (pinfunction "1_1") (pintype "passive"))
      (node (ref "C5") (pin "2") (pinfunction "2_2") (pintype "passive"))
      (node (ref "C51") (pin "2") (pinfunction "2_2") (pintype "passive"))
      (node (ref "C52") (pin "1") (pinfunction "1_1") (pintype "passive"))
      (node (ref "C53") (pin "2") (pinfunction "2_2") (pintype "passive"))
      (node (ref "C54") (pin "1") (pinfunction "1_1") (pintype "passive"))
      (node (ref "C6") (pin "1") (pinfunction "1_1") (pintype "passive"))
      (node (ref "C7") (pin "2") (pinfunction "2_2") (pintype "passive"))
      (node (ref "C8") (pin "1") (pinfunction "1_1") (pintype "passive"))
      (node (ref "C9") (pin "2") (pinfunction "2_2") (pintype "passive"))
      (node (ref "FB_IN") (pin "SLEEVE") (pinfunction "SLEEVE_SLEEVE") (pintype "bidirectional"))
      (node (ref "IC1") (pin "10") (pinfunction "+IN_10") (pintype "input"))
      (node (ref "IC1") (pin "12") (pinfunction "+IN_12") (pintype "input"))
      (node (ref "IC1") (pin "3") (pinfunction "+IN_3") (pintype "input"))
      (node (ref "IC5") (pin "GND") (pinfunction "GND_GND") (pintype "input"))
      (node (ref "IC6") (pin "GND") (pinfunction "GND_GND") (pintype "input"))
      (node (ref "J2") (pin "4") (pinfunction "4_4") (pintype "bidirectional"))
      (node (ref "J36") (pin "3") (pinfunction "3_3") (pintype "bidirectional"))
      (node (ref "J36") (pin "4") (pinfunction "4_4") (pintype "bidirectional"))
      (node (ref "JP14") (pin "2") (pinfunction "2_2") (pintype "passive"))
      (node (ref "JP3") (pin "3") (pinfunction "3_3") (pintype "passive"))
      (node (ref "JP3") (pin "4") (pinfunction "4_4") (pintype "passive"))
      (node (ref "JP3") (pin "5") (pinfunction "5_5") (pintype "passive"))
      (node (ref "JP3") (pin "6") (pinfunction "6_6") (pintype "passive"))
      (node (ref "JP4") (pin "3") (pinfunction "3_3") (pintype "passive"))
      (node (ref "JP4") (pin "4") (pinfunction "4_4") (pintype "passive"))
      (node (ref "JP4") (pin "5") (pinfunction "5_5") (pintype "passive"))
      (node (ref "JP4") (pin "6") (pinfunction "6_6") (pintype "passive"))
      (node (ref "JP5") (pin "3") (pinfunction "3_3") (pintype "passive"))
      (node (ref "JP5") (pin "4") (pinfunction "4_4") (pintype "passive"))
      (node (ref "JP5") (pin "5") (pinfunction "5_5") (pintype "passive"))
      (node (ref "JP5") (pin "6") (pinfunction "6_6") (pintype "passive"))
      (node (ref "MONO_OUT") (pin "SLEEVE") (pinfunction "SLEEVE_SLEEVE") (pintype "bidirectional"))
      (node (ref "R11") (pin "1") (pinfunction "1_1") (pintype "passive"))
      (node (ref "R185") (pin "2") (pinfunction "2_2") (pintype "passive"))
      (node (ref "STEREO_OUT") (pin "SLEEVE") (pinfunction "SLEEVE_SLEEVE") (pintype "bidirectional"))
      (node (ref "U$3") (pin "P$4") (pinfunction "0_P$4") (pintype "bidirectional"))
    )
    (net (code "67") (name "DGND4") (class "Default")
      (node (ref "C1") (pin "2") (pinfunction "2_2") (pintype "passive"))
      (node (ref "C119") (pin "2") (pinfunction "2_2") (pintype "passive"))
      (node (ref "C120") (pin "2") (pinfunction "2_2") (pintype "passive"))
      (node (ref "C2") (pin "2") (pinfunction "2_2") (pintype "passive"))
      (node (ref "DGND5") (pin "1") (pinfunction "1_1") (pintype "passive"))
      (node (ref "JP10") (pin "24") (pinfunction "24_24") (pintype "passive"))
      (node (ref "JP11") (pin "22") (pinfunction "22_22") (pintype "passive"))
      (node (ref "JP6") (pin "20") (pinfunction "20_20") (pintype "passive"))
      (node (ref "JP7") (pin "20") (pinfunction "20_20") (pintype "passive"))
      (node (ref "JP8") (pin "20") (pinfunction "20_20") (pintype "passive"))
      (node (ref "JP9") (pin "22") (pinfunction "22_22") (pintype "passive"))
      (node (ref "JP9") (pin "24") (pinfunction "24_24") (pintype "passive"))
      (node (ref "R111") (pin "2") (pinfunction "2_2") (pintype "passive"))
      (node (ref "R185") (pin "1") (pinfunction "1_1") (pintype "passive"))
      (node (ref "U17") (pin "GND") (pinfunction "GND_GND") (pintype "input"))
      (node (ref "X7") (pin "2") (pinfunction "KL_2") (pintype "passive"))
      (node (ref "X7") (pin "4") (pinfunction "KL_4") (pintype "passive"))
    )
    (net (code "68") (name "GND-ISO") (class "Default")
      (node (ref "C162") (pin "2") (pinfunction "2_2") (pintype "passive"))
      (node (ref "C164") (pin "2") (pinfunction "2_2") (pintype "passive"))
      (node (ref "J1") (pin "4") (pinfunction "4_4") (pintype "bidirectional"))
      (node (ref "JP12") (pin "1") (pinfunction "1_1") (pintype "passive"))
      (node (ref "JP13") (pin "1") (pinfunction "1_1") (pintype "passive"))
      (node (ref "JP16") (pin "1") (pinfunction "1_1") (pintype "passive"))
      (node (ref "JP17") (pin "1") (pinfunction "1_1") (pintype "passive"))
      (node (ref "JP18") (pin "1") (pinfunction "1_1") (pintype "passive"))
      (node (ref "JP19") (pin "1") (pinfunction "1_1") (pintype "passive"))
      (node (ref "JP20") (pin "1") (pinfunction "1_1") (pintype "passive"))
      (node (ref "JP21") (pin "1") (pinfunction "1_1") (pintype "passive"))
      (node (ref "U20") (pin "1") (pinfunction "A0_1") (pintype "input"))
      (node (ref "U20") (pin "12") (pinfunction "GND_12") (pintype "power_in"))
      (node (ref "U20") (pin "21") (pinfunction "A2_21") (pintype "input"))
    )
    (net (code "69") (name "MONO_OUTPUT") (class "Default")
      (node (ref "C158") (pin "+") (pinfunction "+_+") (pintype "passive"))
      (node (ref "IC1") (pin "1") (pinfunction "OUT_1") (pintype "output"))
      (node (ref "R159") (pin "2") (pinfunction "2_2") (pintype "passive"))
      (node (ref "R4") (pin "1") (pinfunction "1_1") (pintype "passive"))
    )
    (net (code "70") (name "Net-(3V3A_0A-Pad1)") (class "Default")
      (node (ref "3V3A_0A") (pin "1") (pinfunction "1_1") (pintype "passive"))
      (node (ref "JP10") (pin "12") (pinfunction "12_12") (pintype "passive"))
    )
    (net (code "71") (name "Net-(3V3A_0B-Pad1)") (class "Default")
      (node (ref "3V3A_0B") (pin "1") (pinfunction "1_1") (pintype "passive"))
      (node (ref "JP11") (pin "12") (pinfunction "12_12") (pintype "passive"))
    )
    (net (code "72") (name "Net-(3V3A_0C-Pad1)") (class "Default")
      (node (ref "3V3A_0C") (pin "1") (pinfunction "1_1") (pintype "passive"))
      (node (ref "JP9") (pin "12") (pinfunction "12_12") (pintype "passive"))
    )
    (net (code "73") (name "Net-(C158-Pad-)") (class "Default")
      (node (ref "C158") (pin "-") (pinfunction "-_-") (pintype "passive"))
      (node (ref "R10") (pin "1") (pinfunction "1_1") (pintype "passive"))
    )
    (net (code "74") (name "Net-(IC1A--IN)") (class "Default")
      (node (ref "IC1") (pin "2") (pinfunction "-IN_2") (pintype "input"))
      (node (ref "R159") (pin "1") (pinfunction "1_1") (pintype "passive"))
      (node (ref "R160") (pin "2") (pinfunction "2_2") (pintype "passive"))
      (node (ref "R161") (pin "2") (pinfunction "2_2") (pintype "passive"))
      (node (ref "R162") (pin "2") (pinfunction "2_2") (pintype "passive"))
    )
    (net (code "75") (name "Net-(IC1B-+IN)") (class "Default")
      (node (ref "FB_IN") (pin "TIP") (pinfunction "TIP_TIP") (pintype "bidirectional"))
      (node (ref "IC1") (pin "5") (pinfunction "+IN_5") (pintype "input"))
      (node (ref "J2") (pin "3") (pinfunction "3_3") (pintype "bidirectional"))
    )
    (net (code "76") (name "Net-(IC1C--IN)") (class "Default")
      (node (ref "IC1") (pin "9") (pinfunction "-IN_9") (pintype "input"))
      (node (ref "R33") (pin "2") (pinfunction "2_2") (pintype "passive"))
      (node (ref "R37") (pin "1") (pinfunction "1_1") (pintype "passive"))
      (node (ref "R5") (pin "2") (pinfunction "2_2") (pintype "passive"))
    )
    (net (code "77") (name "Net-(IC1C-OUT)") (class "Default")
      (node (ref "IC1") (pin "8") (pinfunction "OUT_8") (pintype "output"))
      (node (ref "J2") (pin "1") (pinfunction "1_1") (pintype "bidirectional"))
      (node (ref "R37") (pin "2") (pinfunction "2_2") (pintype "passive"))
      (node (ref "STEREO_OUT") (pin "RING") (pinfunction "RING_RING") (pintype "bidirectional"))
    )
    (net (code "78") (name "Net-(IC1D--IN)") (class "Default")
      (node (ref "IC1") (pin "13") (pinfunction "-IN_13") (pintype "input"))
      (node (ref "R34") (pin "2") (pinfunction "2_2") (pintype "passive"))
      (node (ref "R35") (pin "2") (pinfunction "2_2") (pintype "passive"))
      (node (ref "R38") (pin "1") (pinfunction "1_1") (pintype "passive"))
    )
    (net (code "79") (name "Net-(IC1D-OUT)") (class "Default")
      (node (ref "IC1") (pin "14") (pinfunction "OUT_14") (pintype "output"))
      (node (ref "J2") (pin "2") (pinfunction "2_2") (pintype "bidirectional"))
      (node (ref "R38") (pin "2") (pinfunction "2_2") (pintype "passive"))
      (node (ref "STEREO_OUT") (pin "TIP") (pinfunction "TIP_TIP") (pintype "bidirectional"))
    )
    (net (code "80") (name "Net-(J36-Pad1)") (class "Default")
      (node (ref "J36") (pin "1") (pinfunction "1_1") (pintype "bidirectional"))
      (node (ref "J36") (pin "2") (pinfunction "2_2") (pintype "bidirectional"))
      (node (ref "JP14") (pin "1") (pinfunction "1_1") (pintype "passive"))
      (node (ref "MONO_OUT") (pin "TIP") (pinfunction "TIP_TIP") (pintype "bidirectional"))
      (node (ref "R10") (pin "2") (pinfunction "2_2") (pintype "passive"))
      (node (ref "R11") (pin "2") (pinfunction "2_2") (pintype "passive"))
    )
    (net (code "81") (name "Net-(JP1-Pad2)") (class "Default")
      (node (ref "JP1") (pin "2") (pinfunction "2_2") (pintype "passive"))
      (node (ref "JP9") (pin "15") (pinfunction "15_15") (pintype "passive"))
    )
    (net (code "82") (name "Net-(JP1-Pad4)") (class "Default")
      (node (ref "JP1") (pin "4") (pinfunction "4_4") (pintype "passive"))
      (node (ref "JP9") (pin "13") (pinfunction "13_13") (pintype "passive"))
    )
    (net (code "83") (name "Net-(U$3-VIN+)") (class "Default")
      (node (ref "C11") (pin "1") (pinfunction "1_1") (pintype "passive"))
      (node (ref "C121") (pin "1") (pinfunction "1_1") (pintype "passive"))
      (node (ref "R110") (pin "1") (pinfunction "1_1") (pintype "passive"))
      (node (ref "U$3") (pin "P$1") (pinfunction "VIN+_P$1") (pintype "bidirectional"))
      (node (ref "VREGIN") (pin "1") (pinfunction "1_1") (pintype "passive"))
    )
    (net (code "84") (name "Net-(U$3-VIN-)") (class "Default")
      (node (ref "C11") (pin "2") (pinfunction "2_2") (pintype "passive"))
      (node (ref "C121") (pin "2") (pinfunction "2_2") (pintype "passive"))
      (node (ref "R111") (pin "1") (pinfunction "1_1") (pintype "passive"))
      (node (ref "U$3") (pin "P$2") (pinfunction "VIN-_P$2") (pintype "bidirectional"))
      (node (ref "VREGGND") (pin "1") (pinfunction "1_1") (pintype "passive"))
    )
    (net (code "85") (name "Net-(U1-AIN0)") (class "Default")
      (node (ref "U1") (pin "5") (pinfunction "AIN0_5") (pintype "input"))
      (node (ref "VR1") (pin "P$2") (pinfunction "S_P$2") (pintype "passive"))
    )
    (net (code "86") (name "Net-(U1-AIN1)") (class "Default")
      (node (ref "U1") (pin "6") (pinfunction "AIN1_6") (pintype "input"))
      (node (ref "VR2") (pin "P$2") (pinfunction "S_P$2") (pintype "passive"))
    )
    (net (code "87") (name "Net-(U1-AIN2)") (class "Default")
      (node (ref "U1") (pin "7") (pinfunction "AIN2_7") (pintype "input"))
      (node (ref "VR3") (pin "P$2") (pinfunction "S_P$2") (pintype "passive"))
    )
    (net (code "88") (name "Net-(U1-AIN3)") (class "Default")
      (node (ref "U1") (pin "8") (pinfunction "AIN3_8") (pintype "input"))
      (node (ref "VR4") (pin "P$2") (pinfunction "S_P$2") (pintype "passive"))
    )
    (net (code "89") (name "Net-(U1-AIN4)") (class "Default")
      (node (ref "U1") (pin "9") (pinfunction "AIN4_9") (pintype "input"))
      (node (ref "VR5") (pin "P$2") (pinfunction "S_P$2") (pintype "passive"))
    )
    (net (code "90") (name "Net-(U1-AIN5)") (class "Default")
      (node (ref "U1") (pin "10") (pinfunction "AIN5_10") (pintype "input"))
      (node (ref "VR6") (pin "P$2") (pinfunction "S_P$2") (pintype "passive"))
    )
    (net (code "91") (name "Net-(U1-AIN6)") (class "Default")
      (node (ref "U1") (pin "11") (pinfunction "AIN6_11") (pintype "input"))
      (node (ref "VR7") (pin "P$2") (pinfunction "S_P$2") (pintype "passive"))
    )
    (net (code "92") (name "Net-(U1-AIN7)") (class "Default")
      (node (ref "U1") (pin "12") (pinfunction "AIN7_12") (pintype "input"))
      (node (ref "VR8") (pin "P$2") (pinfunction "S_P$2") (pintype "passive"))
    )
    (net (code "93") (name "Net-(U1-SCL)") (class "Default")
      (node (ref "J1") (pin "1") (pinfunction "1_1") (pintype "bidirectional"))
      (node (ref "U1") (pin "13") (pinfunction "SCL_13") (pintype "input"))
      (node (ref "U20") (pin "22") (pinfunction "SCL_22") (pintype "input"))
    )
    (net (code "94") (name "Net-(U1-SDA)") (class "Default")
      (node (ref "J1") (pin "2") (pinfunction "2_2") (pintype "bidirectional"))
      (node (ref "U1") (pin "14") (pinfunction "SDA_14") (pintype "bidirectional"))
      (node (ref "U20") (pin "23") (pinfunction "SDA_23") (pintype "bidirectional"))
    )
    (net (code "95") (name "Net-(U3-A)") (class "Default")
      (node (ref "R2") (pin "1") (pinfunction "1_1") (pintype "passive"))
      (node (ref "U3") (pin "1") (pinfunction "A_1") (pintype "bidirectional"))
    )
    (net (code "96") (name "Net-(U4-A)") (class "Default")
      (node (ref "R6") (pin "1") (pinfunction "1_1") (pintype "passive"))
      (node (ref "U4") (pin "1") (pinfunction "A_1") (pintype "bidirectional"))
    )
    (net (code "97") (name "Net-(U5-A)") (class "Default")
      (node (ref "R8") (pin "1") (pinfunction "1_1") (pintype "passive"))
      (node (ref "U5") (pin "1") (pinfunction "A_1") (pintype "bidirectional"))
    )
    (net (code "98") (name "Net-(U6-A)") (class "Default")
      (node (ref "R16") (pin "1") (pinfunction "1_1") (pintype "passive"))
      (node (ref "U6") (pin "1") (pinfunction "A_1") (pintype "bidirectional"))
    )
    (net (code "99") (name "Net-(U7-A)") (class "Default")
      (node (ref "R18") (pin "1") (pinfunction "1_1") (pintype "passive"))
      (node (ref "U7") (pin "1") (pinfunction "A_1") (pintype "bidirectional"))
    )
    (net (code "100") (name "Net-(U8-A)") (class "Default")
      (node (ref "R20") (pin "1") (pinfunction "1_1") (pintype "passive"))
      (node (ref "U8") (pin "1") (pinfunction "A_1") (pintype "bidirectional"))
    )
    (net (code "101") (name "Net-(U9-A)") (class "Default")
      (node (ref "R22") (pin "1") (pinfunction "1_1") (pintype "passive"))
      (node (ref "U9") (pin "1") (pinfunction "A_1") (pintype "bidirectional"))
    )
    (net (code "102") (name "Net-(U10-A)") (class "Default")
      (node (ref "R26") (pin "1") (pinfunction "1_1") (pintype "passive"))
      (node (ref "U10") (pin "1") (pinfunction "A_1") (pintype "bidirectional"))
    )
    (net (code "103") (name "Net-(U11-A)") (class "Default")
      (node (ref "R28") (pin "1") (pinfunction "1_1") (pintype "passive"))
      (node (ref "U11") (pin "1") (pinfunction "A_1") (pintype "bidirectional"))
    )
    (net (code "104") (name "Net-(U12-A)") (class "Default")
      (node (ref "R30") (pin "1") (pinfunction "1_1") (pintype "passive"))
      (node (ref "U12") (pin "1") (pinfunction "A_1") (pintype "bidirectional"))
    )
    (net (code "105") (name "Net-(U13-A)") (class "Default")
      (node (ref "R32") (pin "1") (pinfunction "1_1") (pintype "passive"))
      (node (ref "U13") (pin "1") (pinfunction "A_1") (pintype "bidirectional"))
    )
    (net (code "106") (name "Net-(U14-A)") (class "Default")
      (node (ref "R24") (pin "1") (pinfunction "1_1") (pintype "passive"))
      (node (ref "U14") (pin "1") (pinfunction "A_1") (pintype "bidirectional"))
    )
    (net (code "107") (name "Net-(U20-A1)") (class "Default")
      (node (ref "R125") (pin "2") (pinfunction "2_2") (pintype "passive"))
      (node (ref "U20") (pin "2") (pinfunction "A1_2") (pintype "input"))
    )
    (net (code "108") (name "Net-(U20-~{RESET})") (class "Default")
      (node (ref "R134") (pin "1") (pinfunction "1_1") (pintype "passive"))
      (node (ref "U20") (pin "3") (pinfunction "~{RESET}_3") (pintype "input"))
    )
    (net (code "109") (name "Net-(X6I-KL)") (class "Default")
      (node (ref "JP22") (pin "1") (pinfunction "1_1") (pintype "passive"))
      (node (ref "X6") (pin "17") (pinfunction "KL_17") (pintype "passive"))
    )
    (net (code "110") (name "Net-(X6J-KL)") (class "Default")
      (node (ref "JP23") (pin "1") (pinfunction "1_1") (pintype "passive"))
      (node (ref "X6") (pin "18") (pinfunction "KL_18") (pintype "passive"))
    )
    (net (code "111") (name "Net-(X6K-KL)") (class "Default")
      (node (ref "JP24") (pin "1") (pinfunction "1_1") (pintype "passive"))
      (node (ref "X6") (pin "19") (pinfunction "KL_19") (pintype "passive"))
    )
    (net (code "112") (name "Net-(X6M-KL)") (class "Default")
      (node (ref "JP25") (pin "1") (pinfunction "1_1") (pintype "passive"))
      (node (ref "X6") (pin "20") (pinfunction "KL_20") (pintype "passive"))
    )
    (net (code "113") (name "Net-(X7C-KL)") (class "Default")
      (node (ref "R208") (pin "2") (pinfunction "2_2") (pintype "passive"))
      (node (ref "X7") (pin "11") (pinfunction "KL_11") (pintype "passive"))
    )
    (net (code "114") (name "Net-(X7G-KL)") (class "Default")
      (node (ref "R209") (pin "2") (pinfunction "2_2") (pintype "passive"))
      (node (ref "X7") (pin "15") (pinfunction "KL_15") (pintype "passive"))
    )
    (net (code "115") (name "Net-(X7N-KL)") (class "Default")
      (node (ref "R112") (pin "2") (pinfunction "2_2") (pintype "passive"))
      (node (ref "X7") (pin "7") (pinfunction "KL_7") (pintype "passive"))
    )
    (net (code "116") (name "REG+12V") (class "Default")
      (node (ref "+15VA") (pin "1") (pinfunction "1_1") (pintype "passive"))
      (node (ref "C53") (pin "1") (pinfunction "1_1") (pintype "passive"))
      (node (ref "C9") (pin "1") (pinfunction "1_1") (pintype "passive"))
      (node (ref "IC5") (pin "IN") (pinfunction "IN_IN") (pintype "input"))
      (node (ref "U$3") (pin "P$5") (pinfunction "12VOUT_P$5") (pintype "bidirectional"))
    )
    (net (code "117") (name "REG-12V") (class "Default")
      (node (ref "-15VA") (pin "1") (pinfunction "1_1") (pintype "passive"))
      (node (ref "C10") (pin "2") (pinfunction "2_2") (pintype "passive"))
      (node (ref "C54") (pin "2") (pinfunction "2_2") (pintype "passive"))
      (node (ref "IC6") (pin "IN") (pinfunction "IN_IN") (pintype "input"))
      (node (ref "U$3") (pin "P$3") (pinfunction "-12VOUT_P$3") (pintype "bidirectional"))
    )
    (net (code "118") (name "SC0") (class "Default")
      (node (ref "JP12") (pin "3") (pinfunction "3_3") (pintype "passive"))
      (node (ref "U20") (pin "5") (pinfunction "SC0_5") (pintype "bidirectional"))
    )
    (net (code "119") (name "SC1") (class "Default")
      (node (ref "JP13") (pin "3") (pinfunction "3_3") (pintype "passive"))
      (node (ref "U20") (pin "7") (pinfunction "SC1_7") (pintype "bidirectional"))
    )
    (net (code "120") (name "SC2") (class "Default")
      (node (ref "JP16") (pin "3") (pinfunction "3_3") (pintype "passive"))
      (node (ref "U20") (pin "9") (pinfunction "SC2_9") (pintype "bidirectional"))
    )
    (net (code "121") (name "SC3") (class "Default")
      (node (ref "JP17") (pin "3") (pinfunction "3_3") (pintype "passive"))
      (node (ref "U20") (pin "11") (pinfunction "SC3_11") (pintype "bidirectional"))
    )
    (net (code "122") (name "SC4") (class "Default")
      (node (ref "JP18") (pin "3") (pinfunction "3_3") (pintype "passive"))
      (node (ref "U20") (pin "14") (pinfunction "SC4_14") (pintype "bidirectional"))
    )
    (net (code "123") (name "SC5") (class "Default")
      (node (ref "JP19") (pin "3") (pinfunction "3_3") (pintype "passive"))
      (node (ref "U20") (pin "16") (pinfunction "SC5_16") (pintype "bidirectional"))
    )
    (net (code "124") (name "SC6") (class "Default")
      (node (ref "JP20") (pin "3") (pinfunction "3_3") (pintype "passive"))
      (node (ref "U20") (pin "18") (pinfunction "SC6_18") (pintype "bidirectional"))
    )
    (net (code "125") (name "SC7") (class "Default")
      (node (ref "JP21") (pin "3") (pinfunction "3_3") (pintype "passive"))
      (node (ref "U20") (pin "20") (pinfunction "SC7_20") (pintype "bidirectional"))
    )
    (net (code "126") (name "SD0") (class "Default")
      (node (ref "JP12") (pin "4") (pinfunction "4_4") (pintype "passive"))
      (node (ref "U20") (pin "4") (pinfunction "SD0_4") (pintype "bidirectional"))
    )
    (net (code "127") (name "SD1") (class "Default")
      (node (ref "JP13") (pin "4") (pinfunction "4_4") (pintype "passive"))
      (node (ref "U20") (pin "6") (pinfunction "SD1_6") (pintype "bidirectional"))
    )
    (net (code "128") (name "SD2") (class "Default")
      (node (ref "JP16") (pin "4") (pinfunction "4_4") (pintype "passive"))
      (node (ref "U20") (pin "8") (pinfunction "SD2_8") (pintype "bidirectional"))
    )
    (net (code "129") (name "SD3") (class "Default")
      (node (ref "JP17") (pin "4") (pinfunction "4_4") (pintype "passive"))
      (node (ref "U20") (pin "10") (pinfunction "SD3_10") (pintype "bidirectional"))
    )
    (net (code "130") (name "SD4") (class "Default")
      (node (ref "JP18") (pin "4") (pinfunction "4_4") (pintype "passive"))
      (node (ref "U20") (pin "13") (pinfunction "SD4_13") (pintype "bidirectional"))
    )
    (net (code "131") (name "SD5") (class "Default")
      (node (ref "JP19") (pin "4") (pinfunction "4_4") (pintype "passive"))
      (node (ref "U20") (pin "15") (pinfunction "SD5_15") (pintype "bidirectional"))
    )
    (net (code "132") (name "SD6") (class "Default")
      (node (ref "JP20") (pin "4") (pinfunction "4_4") (pintype "passive"))
      (node (ref "U20") (pin "17") (pinfunction "SD6_17") (pintype "bidirectional"))
    )
    (net (code "133") (name "SD7") (class "Default")
      (node (ref "JP21") (pin "4") (pinfunction "4_4") (pintype "passive"))
      (node (ref "U20") (pin "19") (pinfunction "SD7_19") (pintype "bidirectional"))
    )
    (net (code "134") (name "SUPPLY0_CGND_") (class "Default")
      (node (ref "C123") (pin "2") (pinfunction "2_2") (pintype "passive"))
      (node (ref "C15") (pin "2") (pinfunction "2_2") (pintype "passive"))
      (node (ref "C16") (pin "2") (pinfunction "2_2") (pintype "passive"))
      (node (ref "C182") (pin "2") (pinfunction "2_2") (pintype "passive"))
      (node (ref "C21") (pin "2") (pinfunction "2_2") (pintype "passive"))
      (node (ref "C22") (pin "2") (pinfunction "2_2") (pintype "passive"))
      (node (ref "DGND4") (pin "1") (pinfunction "1_1") (pintype "passive"))
      (node (ref "U10") (pin "2") (pinfunction "K_2") (pintype "bidirectional"))
      (node (ref "U10") (pin "4") (pinfunction "E_4") (pintype "bidirectional"))
      (node (ref "U11") (pin "2") (pinfunction "K_2") (pintype "bidirectional"))
      (node (ref "U11") (pin "4") (pinfunction "E_4") (pintype "bidirectional"))
      (node (ref "U12") (pin "2") (pinfunction "K_2") (pintype "bidirectional"))
      (node (ref "U12") (pin "4") (pinfunction "E_4") (pintype "bidirectional"))
      (node (ref "U13") (pin "2") (pinfunction "K_2") (pintype "bidirectional"))
      (node (ref "U13") (pin "4") (pinfunction "E_4") (pintype "bidirectional"))
      (node (ref "U14") (pin "2") (pinfunction "K_2") (pintype "bidirectional"))
      (node (ref "U14") (pin "4") (pinfunction "E_4") (pintype "bidirectional"))
      (node (ref "U16") (pin "2") (pinfunction "GND_2") (pintype "power_in"))
      (node (ref "U3") (pin "2") (pinfunction "K_2") (pintype "bidirectional"))
      (node (ref "U3") (pin "4") (pinfunction "E_4") (pintype "bidirectional"))
      (node (ref "U4") (pin "2") (pinfunction "K_2") (pintype "bidirectional"))
      (node (ref "U4") (pin "4") (pinfunction "E_4") (pintype "bidirectional"))
      (node (ref "U5") (pin "2") (pinfunction "K_2") (pintype "bidirectional"))
      (node (ref "U5") (pin "4") (pinfunction "E_4") (pintype "bidirectional"))
      (node (ref "U6") (pin "2") (pinfunction "K_2") (pintype "bidirectional"))
      (node (ref "U6") (pin "4") (pinfunction "E_4") (pintype "bidirectional"))
      (node (ref "U7") (pin "2") (pinfunction "K_2") (pintype "bidirectional"))
      (node (ref "U7") (pin "4") (pinfunction "E_4") (pintype "bidirectional"))
      (node (ref "U8") (pin "2") (pinfunction "K_2") (pintype "bidirectional"))
      (node (ref "U8") (pin "4") (pinfunction "E_4") (pintype "bidirectional"))
      (node (ref "U9") (pin "2") (pinfunction "K_2") (pintype "bidirectional"))
      (node (ref "U9") (pin "4") (pinfunction "E_4") (pintype "bidirectional"))
      (node (ref "X10") (pin "13") (pinfunction "KL_13") (pintype "passive"))
      (node (ref "X10") (pin "15") (pinfunction "KL_15") (pintype "passive"))
    )
    (net (code "135") (name "unconnected-(FB_IN-PadRING)") (class "Default")
      (node (ref "FB_IN") (pin "RING") (pinfunction "RING_RING") (pintype "bidirectional"))
    )
    (net (code "136") (name "unconnected-(FB_IN-PadRSH)") (class "Default")
      (node (ref "FB_IN") (pin "RSH") (pinfunction "RSH_RSH") (pintype "bidirectional"))
    )
    (net (code "137") (name "unconnected-(FB_IN-PadTSH)") (class "Default")
      (node (ref "FB_IN") (pin "TSH") (pinfunction "TSH_TSH") (pintype "bidirectional"))
    )
    (net (code "138") (name "unconnected-(JP6-Pad1)") (class "Default")
      (node (ref "JP6") (pin "1") (pinfunction "1_1") (pintype "passive"))
    )
    (net (code "139") (name "unconnected-(JP6-Pad2)") (class "Default")
      (node (ref "JP6") (pin "2") (pinfunction "2_2") (pintype "passive"))
    )
    (net (code "140") (name "unconnected-(JP6-Pad7)") (class "Default")
      (node (ref "JP6") (pin "7") (pinfunction "7_7") (pintype "passive"))
    )
    (net (code "141") (name "unconnected-(JP6-Pad8)") (class "Default")
      (node (ref "JP6") (pin "8") (pinfunction "8_8") (pintype "passive"))
    )
    (net (code "142") (name "unconnected-(JP6-Pad9)") (class "Default")
      (node (ref "JP6") (pin "9") (pinfunction "9_9") (pintype "passive"))
    )
    (net (code "143") (name "unconnected-(JP6-Pad10)") (class "Default")
      (node (ref "JP6") (pin "10") (pinfunction "10_10") (pintype "passive"))
    )
    (net (code "144") (name "unconnected-(JP6-Pad11)") (class "Default")
      (node (ref "JP6") (pin "11") (pinfunction "11_11") (pintype "passive"))
    )
    (net (code "145") (name "unconnected-(JP6-Pad12)") (class "Default")
      (node (ref "JP6") (pin "12") (pinfunction "12_12") (pintype "passive"))
    )
    (net (code "146") (name "unconnected-(JP6-Pad13)") (class "Default")
      (node (ref "JP6") (pin "13") (pinfunction "13_13") (pintype "passive"))
    )
    (net (code "147") (name "unconnected-(JP6-Pad14)") (class "Default")
      (node (ref "JP6") (pin "14") (pinfunction "14_14") (pintype "passive"))
    )
    (net (code "148") (name "unconnected-(JP6-Pad15)") (class "Default")
      (node (ref "JP6") (pin "15") (pinfunction "15_15") (pintype "passive"))
    )
    (net (code "149") (name "unconnected-(JP6-Pad16)") (class "Default")
      (node (ref "JP6") (pin "16") (pinfunction "16_16") (pintype "passive"))
    )
    (net (code "150") (name "unconnected-(JP6-Pad17)") (class "Default")
      (node (ref "JP6") (pin "17") (pinfunction "17_17") (pintype "passive"))
    )
    (net (code "151") (name "unconnected-(JP6-Pad18)") (class "Default")
      (node (ref "JP6") (pin "18") (pinfunction "18_18") (pintype "passive"))
    )
    (net (code "152") (name "unconnected-(JP7-Pad1)") (class "Default")
      (node (ref "JP7") (pin "1") (pinfunction "1_1") (pintype "passive"))
    )
    (net (code "153") (name "unconnected-(JP7-Pad2)") (class "Default")
      (node (ref "JP7") (pin "2") (pinfunction "2_2") (pintype "passive"))
    )
    (net (code "154") (name "unconnected-(JP7-Pad7)") (class "Default")
      (node (ref "JP7") (pin "7") (pinfunction "7_7") (pintype "passive"))
    )
    (net (code "155") (name "unconnected-(JP7-Pad8)") (class "Default")
      (node (ref "JP7") (pin "8") (pinfunction "8_8") (pintype "passive"))
    )
    (net (code "156") (name "unconnected-(JP7-Pad9)") (class "Default")
      (node (ref "JP7") (pin "9") (pinfunction "9_9") (pintype "passive"))
    )
    (net (code "157") (name "unconnected-(JP7-Pad10)") (class "Default")
      (node (ref "JP7") (pin "10") (pinfunction "10_10") (pintype "passive"))
    )
    (net (code "158") (name "unconnected-(JP7-Pad11)") (class "Default")
      (node (ref "JP7") (pin "11") (pinfunction "11_11") (pintype "passive"))
    )
    (net (code "159") (name "unconnected-(JP7-Pad12)") (class "Default")
      (node (ref "JP7") (pin "12") (pinfunction "12_12") (pintype "passive"))
    )
    (net (code "160") (name "unconnected-(JP7-Pad13)") (class "Default")
      (node (ref "JP7") (pin "13") (pinfunction "13_13") (pintype "passive"))
    )
    (net (code "161") (name "unconnected-(JP7-Pad14)") (class "Default")
      (node (ref "JP7") (pin "14") (pinfunction "14_14") (pintype "passive"))
    )
    (net (code "162") (name "unconnected-(JP7-Pad15)") (class "Default")
      (node (ref "JP7") (pin "15") (pinfunction "15_15") (pintype "passive"))
    )
    (net (code "163") (name "unconnected-(JP7-Pad16)") (class "Default")
      (node (ref "JP7") (pin "16") (pinfunction "16_16") (pintype "passive"))
    )
    (net (code "164") (name "unconnected-(JP7-Pad17)") (class "Default")
      (node (ref "JP7") (pin "17") (pinfunction "17_17") (pintype "passive"))
    )
    (net (code "165") (name "unconnected-(JP7-Pad18)") (class "Default")
      (node (ref "JP7") (pin "18") (pinfunction "18_18") (pintype "passive"))
    )
    (net (code "166") (name "unconnected-(JP8-Pad1)") (class "Default")
      (node (ref "JP8") (pin "1") (pinfunction "1_1") (pintype "passive"))
    )
    (net (code "167") (name "unconnected-(JP8-Pad2)") (class "Default")
      (node (ref "JP8") (pin "2") (pinfunction "2_2") (pintype "passive"))
    )
    (net (code "168") (name "unconnected-(JP8-Pad7)") (class "Default")
      (node (ref "JP8") (pin "7") (pinfunction "7_7") (pintype "passive"))
    )
    (net (code "169") (name "unconnected-(JP8-Pad8)") (class "Default")
      (node (ref "JP8") (pin "8") (pinfunction "8_8") (pintype "passive"))
    )
    (net (code "170") (name "unconnected-(JP8-Pad9)") (class "Default")
      (node (ref "JP8") (pin "9") (pinfunction "9_9") (pintype "passive"))
    )
    (net (code "171") (name "unconnected-(JP8-Pad10)") (class "Default")
      (node (ref "JP8") (pin "10") (pinfunction "10_10") (pintype "passive"))
    )
    (net (code "172") (name "unconnected-(JP8-Pad11)") (class "Default")
      (node (ref "JP8") (pin "11") (pinfunction "11_11") (pintype "passive"))
    )
    (net (code "173") (name "unconnected-(JP8-Pad12)") (class "Default")
      (node (ref "JP8") (pin "12") (pinfunction "12_12") (pintype "passive"))
    )
    (net (code "174") (name "unconnected-(JP8-Pad13)") (class "Default")
      (node (ref "JP8") (pin "13") (pinfunction "13_13") (pintype "passive"))
    )
    (net (code "175") (name "unconnected-(JP8-Pad14)") (class "Default")
      (node (ref "JP8") (pin "14") (pinfunction "14_14") (pintype "passive"))
    )
    (net (code "176") (name "unconnected-(JP8-Pad15)") (class "Default")
      (node (ref "JP8") (pin "15") (pinfunction "15_15") (pintype "passive"))
    )
    (net (code "177") (name "unconnected-(JP8-Pad16)") (class "Default")
      (node (ref "JP8") (pin "16") (pinfunction "16_16") (pintype "passive"))
    )
    (net (code "178") (name "unconnected-(JP8-Pad17)") (class "Default")
      (node (ref "JP8") (pin "17") (pinfunction "17_17") (pintype "passive"))
    )
    (net (code "179") (name "unconnected-(JP8-Pad18)") (class "Default")
      (node (ref "JP8") (pin "18") (pinfunction "18_18") (pintype "passive"))
    )
    (net (code "180") (name "unconnected-(JP9-Pad1)") (class "Default")
      (node (ref "JP9") (pin "1") (pinfunction "1_1") (pintype "passive"))
    )
    (net (code "181") (name "unconnected-(JP9-Pad2)") (class "Default")
      (node (ref "JP9") (pin "2") (pinfunction "2_2") (pintype "passive"))
    )
    (net (code "182") (name "unconnected-(JP9-Pad3)") (class "Default")
      (node (ref "JP9") (pin "3") (pinfunction "3_3") (pintype "passive"))
    )
    (net (code "183") (name "unconnected-(JP9-Pad4)") (class "Default")
      (node (ref "JP9") (pin "4") (pinfunction "4_4") (pintype "passive"))
    )
    (net (code "184") (name "unconnected-(JP9-Pad5)") (class "Default")
      (node (ref "JP9") (pin "5") (pinfunction "5_5") (pintype "passive"))
    )
    (net (code "185") (name "unconnected-(JP9-Pad6)") (class "Default")
      (node (ref "JP9") (pin "6") (pinfunction "6_6") (pintype "passive"))
    )
    (net (code "186") (name "unconnected-(JP9-Pad11)") (class "Default")
      (node (ref "JP9") (pin "11") (pinfunction "11_11") (pintype "passive"))
    )
    (net (code "187") (name "unconnected-(JP9-Pad21)") (class "Default")
      (node (ref "JP9") (pin "21") (pinfunction "21_21") (pintype "passive"))
    )
    (net (code "188") (name "unconnected-(JP9-Pad23)") (class "Default")
      (node (ref "JP9") (pin "23") (pinfunction "23_23") (pintype "passive"))
    )
    (net (code "189") (name "unconnected-(JP9-Pad25)") (class "Default")
      (node (ref "JP9") (pin "25") (pinfunction "25_25") (pintype "passive"))
    )
    (net (code "190") (name "unconnected-(JP9-Pad26)") (class "Default")
      (node (ref "JP9") (pin "26") (pinfunction "26_26") (pintype "passive"))
    )
    (net (code "191") (name "unconnected-(JP9-Pad27)") (class "Default")
      (node (ref "JP9") (pin "27") (pinfunction "27_27") (pintype "passive"))
    )
    (net (code "192") (name "unconnected-(JP9-Pad28)") (class "Default")
      (node (ref "JP9") (pin "28") (pinfunction "28_28") (pintype "passive"))
    )
    (net (code "193") (name "unconnected-(JP9-Pad29)") (class "Default")
      (node (ref "JP9") (pin "29") (pinfunction "29_29") (pintype "passive"))
    )
    (net (code "194") (name "unconnected-(JP9-Pad30)") (class "Default")
      (node (ref "JP9") (pin "30") (pinfunction "30_30") (pintype "passive"))
    )
    (net (code "195") (name "unconnected-(JP10-Pad1)") (class "Default")
      (node (ref "JP10") (pin "1") (pinfunction "1_1") (pintype "passive"))
    )
    (net (code "196") (name "unconnected-(JP10-Pad2)") (class "Default")
      (node (ref "JP10") (pin "2") (pinfunction "2_2") (pintype "passive"))
    )
    (net (code "197") (name "unconnected-(JP10-Pad3)") (class "Default")
      (node (ref "JP10") (pin "3") (pinfunction "3_3") (pintype "passive"))
    )
    (net (code "198") (name "unconnected-(JP10-Pad4)") (class "Default")
      (node (ref "JP10") (pin "4") (pinfunction "4_4") (pintype "passive"))
    )
    (net (code "199") (name "unconnected-(JP10-Pad5)") (class "Default")
      (node (ref "JP10") (pin "5") (pinfunction "5_5") (pintype "passive"))
    )
    (net (code "200") (name "unconnected-(JP10-Pad6)") (class "Default")
      (node (ref "JP10") (pin "6") (pinfunction "6_6") (pintype "passive"))
    )
    (net (code "201") (name "unconnected-(JP10-Pad11)") (class "Default")
      (node (ref "JP10") (pin "11") (pinfunction "11_11") (pintype "passive"))
    )
    (net (code "202") (name "unconnected-(JP10-Pad21)") (class "Default")
      (node (ref "JP10") (pin "21") (pinfunction "21_21") (pintype "passive"))
    )
    (net (code "203") (name "unconnected-(JP10-Pad22)") (class "Default")
      (node (ref "JP10") (pin "22") (pinfunction "22_22") (pintype "passive"))
    )
    (net (code "204") (name "unconnected-(JP10-Pad23)") (class "Default")
      (node (ref "JP10") (pin "23") (pinfunction "23_23") (pintype "passive"))
    )
    (net (code "205") (name "unconnected-(JP10-Pad25)") (class "Default")
      (node (ref "JP10") (pin "25") (pinfunction "25_25") (pintype "passive"))
    )
    (net (code "206") (name "unconnected-(JP10-Pad26)") (class "Default")
      (node (ref "JP10") (pin "26") (pinfunction "26_26") (pintype "passive"))
    )
    (net (code "207") (name "unconnected-(JP10-Pad27)") (class "Default")
      (node (ref "JP10") (pin "27") (pinfunction "27_27") (pintype "passive"))
    )
    (net (code "208") (name "unconnected-(JP10-Pad28)") (class "Default")
      (node (ref "JP10") (pin "28") (pinfunction "28_28") (pintype "passive"))
    )
    (net (code "209") (name "unconnected-(JP10-Pad29)") (class "Default")
      (node (ref "JP10") (pin "29") (pinfunction "29_29") (pintype "passive"))
    )
    (net (code "210") (name "unconnected-(JP10-Pad30)") (class "Default")
      (node (ref "JP10") (pin "30") (pinfunction "30_30") (pintype "passive"))
    )
    (net (code "211") (name "unconnected-(JP11-Pad1)") (class "Default")
      (node (ref "JP11") (pin "1") (pinfunction "1_1") (pintype "passive"))
    )
    (net (code "212") (name "unconnected-(JP11-Pad2)") (class "Default")
      (node (ref "JP11") (pin "2") (pinfunction "2_2") (pintype "passive"))
    )
    (net (code "213") (name "unconnected-(JP11-Pad3)") (class "Default")
      (node (ref "JP11") (pin "3") (pinfunction "3_3") (pintype "passive"))
    )
    (net (code "214") (name "unconnected-(JP11-Pad4)") (class "Default")
      (node (ref "JP11") (pin "4") (pinfunction "4_4") (pintype "passive"))
    )
    (net (code "215") (name "unconnected-(JP11-Pad5)") (class "Default")
      (node (ref "JP11") (pin "5") (pinfunction "5_5") (pintype "passive"))
    )
    (net (code "216") (name "unconnected-(JP11-Pad6)") (class "Default")
      (node (ref "JP11") (pin "6") (pinfunction "6_6") (pintype "passive"))
    )
    (net (code "217") (name "unconnected-(JP11-Pad11)") (class "Default")
      (node (ref "JP11") (pin "11") (pinfunction "11_11") (pintype "passive"))
    )
    (net (code "218") (name "unconnected-(JP11-Pad21)") (class "Default")
      (node (ref "JP11") (pin "21") (pinfunction "21_21") (pintype "passive"))
    )
    (net (code "219") (name "unconnected-(JP11-Pad23)") (class "Default")
      (node (ref "JP11") (pin "23") (pinfunction "23_23") (pintype "passive"))
    )
    (net (code "220") (name "unconnected-(JP11-Pad24)") (class "Default")
      (node (ref "JP11") (pin "24") (pinfunction "24_24") (pintype "passive"))
    )
    (net (code "221") (name "unconnected-(JP11-Pad25)") (class "Default")
      (node (ref "JP11") (pin "25") (pinfunction "25_25") (pintype "passive"))
    )
    (net (code "222") (name "unconnected-(JP11-Pad26)") (class "Default")
      (node (ref "JP11") (pin "26") (pinfunction "26_26") (pintype "passive"))
    )
    (net (code "223") (name "unconnected-(JP11-Pad27)") (class "Default")
      (node (ref "JP11") (pin "27") (pinfunction "27_27") (pintype "passive"))
    )
    (net (code "224") (name "unconnected-(JP11-Pad28)") (class "Default")
      (node (ref "JP11") (pin "28") (pinfunction "28_28") (pintype "passive"))
    )
    (net (code "225") (name "unconnected-(JP11-Pad29)") (class "Default")
      (node (ref "JP11") (pin "29") (pinfunction "29_29") (pintype "passive"))
    )
    (net (code "226") (name "unconnected-(JP11-Pad30)") (class "Default")
      (node (ref "JP11") (pin "30") (pinfunction "30_30") (pintype "passive"))
    )
    (net (code "227") (name "unconnected-(MONO_OUT-PadRING)") (class "Default")
      (node (ref "MONO_OUT") (pin "RING") (pinfunction "RING_RING") (pintype "bidirectional"))
    )
    (net (code "228") (name "unconnected-(MONO_OUT-PadRSH)") (class "Default")
      (node (ref "MONO_OUT") (pin "RSH") (pinfunction "RSH_RSH") (pintype "bidirectional"))
    )
    (net (code "229") (name "unconnected-(MONO_OUT-PadTSH)") (class "Default")
      (node (ref "MONO_OUT") (pin "TSH") (pinfunction "TSH_TSH") (pintype "bidirectional"))
    )
    (net (code "230") (name "unconnected-(STEREO_OUT-PadRSH)") (class "Default")
      (node (ref "STEREO_OUT") (pin "RSH") (pinfunction "RSH_RSH") (pintype "bidirectional"))
    )
    (net (code "231") (name "unconnected-(STEREO_OUT-PadTSH)") (class "Default")
      (node (ref "STEREO_OUT") (pin "TSH") (pinfunction "TSH_TSH") (pintype "bidirectional"))
    )
    (net (code "232") (name "unconnected-(U1-NC-Pad4)") (class "Default")
      (node (ref "U1") (pin "4") (pinfunction "NC_4") (pintype "no_connect"))
    )
    (net (code "233") (name "unconnected-(U1-NC_2-Pad2)") (class "Default")
      (node (ref "U1") (pin "2") (pinfunction "NC_2_2") (pintype "no_connect"))
    )
    (net (code "234") (name "unconnected-(U1-NC_3-Pad3)") (class "Default")
      (node (ref "U1") (pin "3") (pinfunction "NC_3_3") (pintype "no_connect"))
    )
    (net (code "235") (name "unconnected-(U1-REF-Pad1)") (class "Default")
      (node (ref "U1") (pin "1") (pinfunction "REF_1") (pintype "bidirectional"))
    )
    (net (code "236") (name "unconnected-(U16-~{OC}-Pad3)") (class "Default")
      (node (ref "U16") (pin "3") (pinfunction "~{OC}_3") (pintype "output"))
    )
  )
)
